# uRinks_v2_0.net
KiCad netlist of a schematic drawn in EAGLE
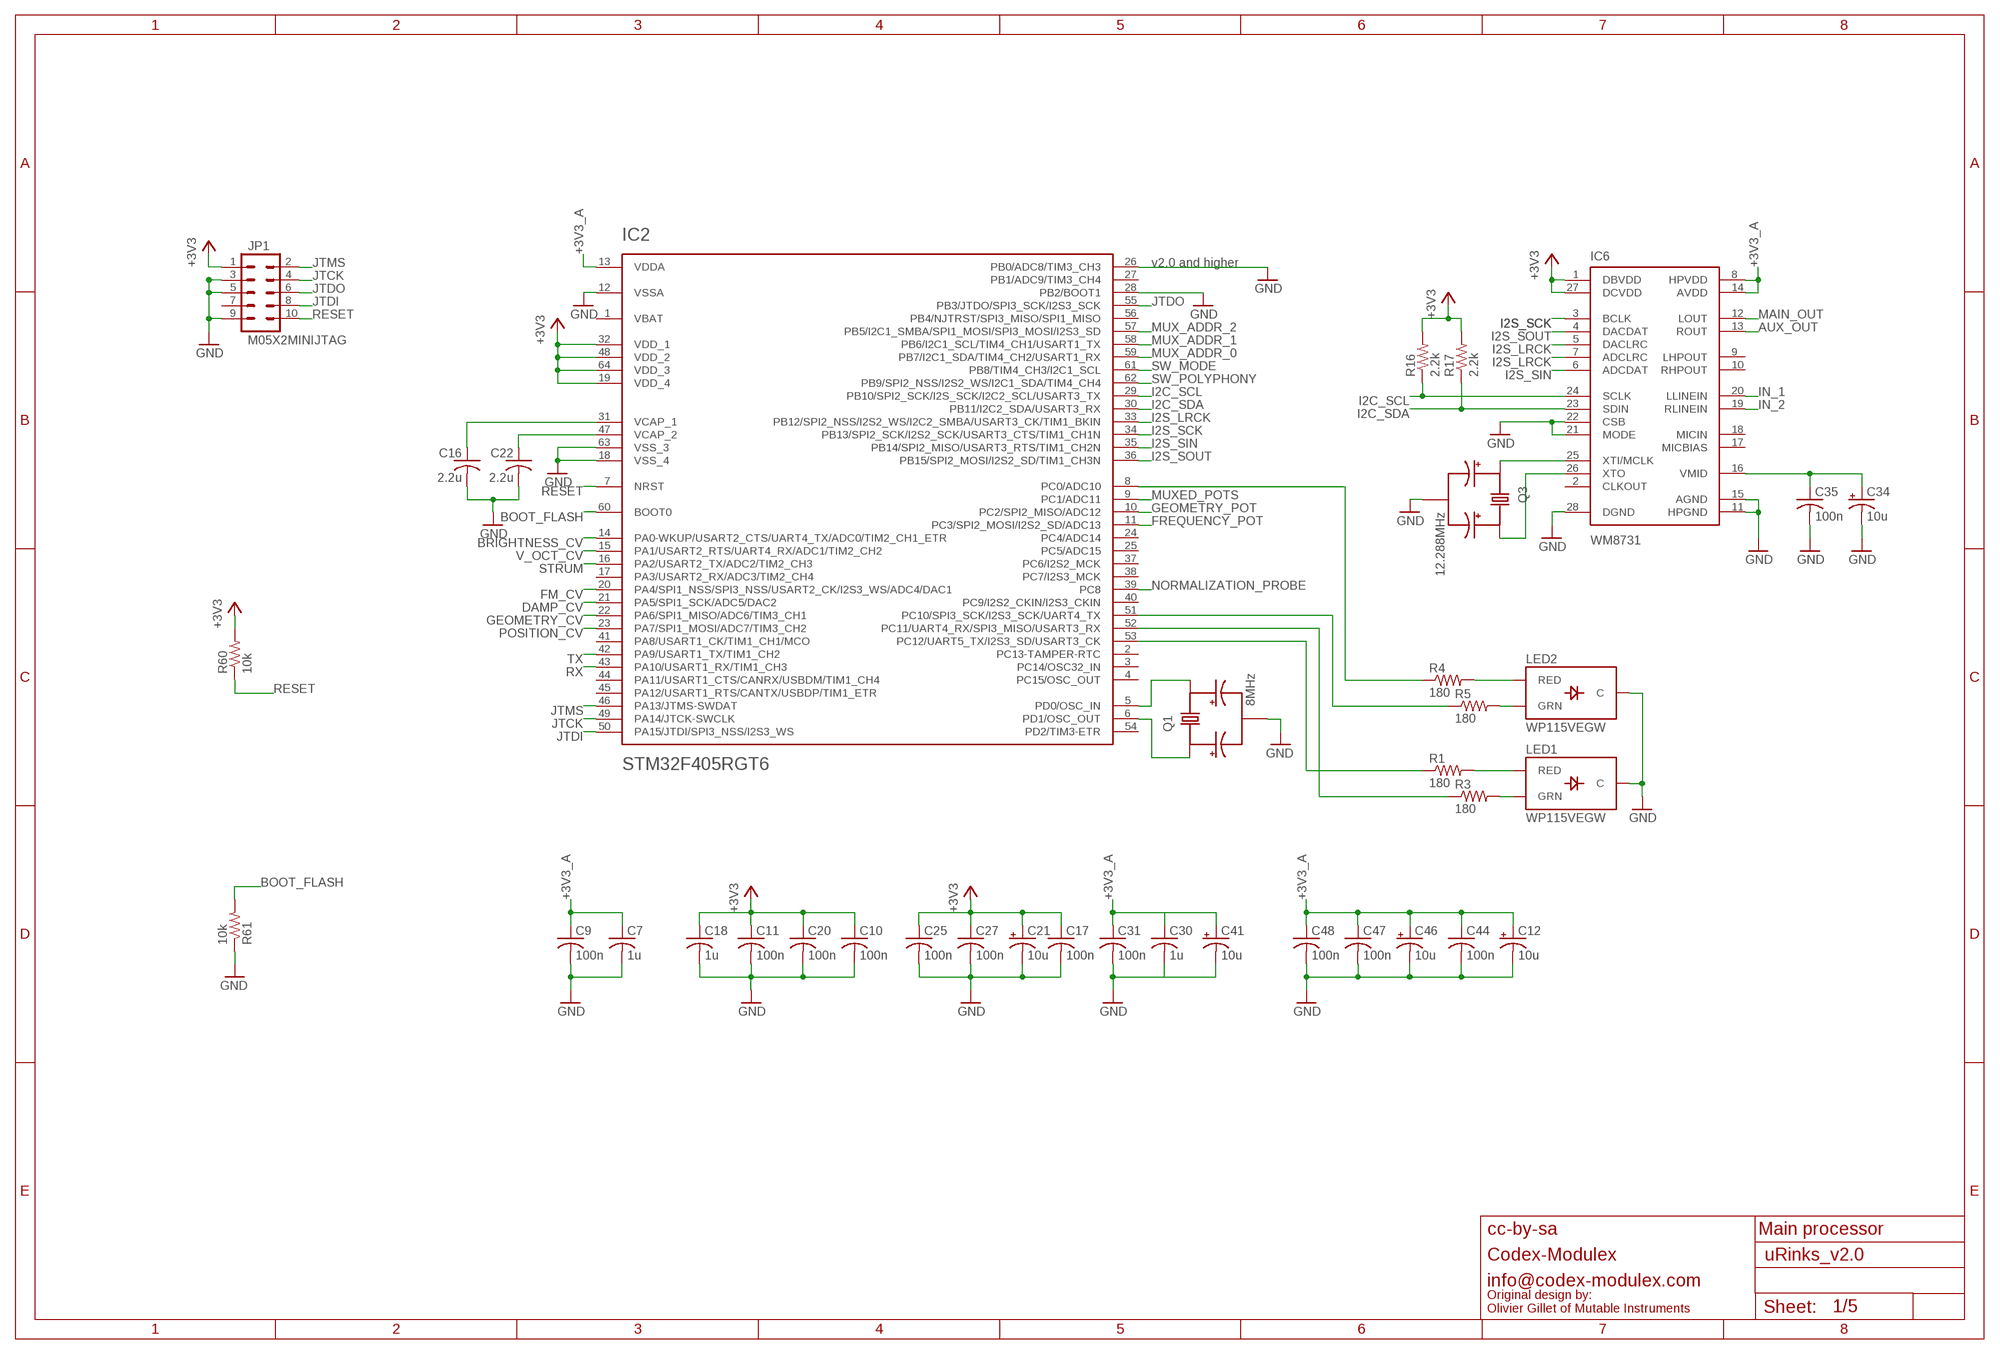
[diagram p0: schematic, sheet 1]
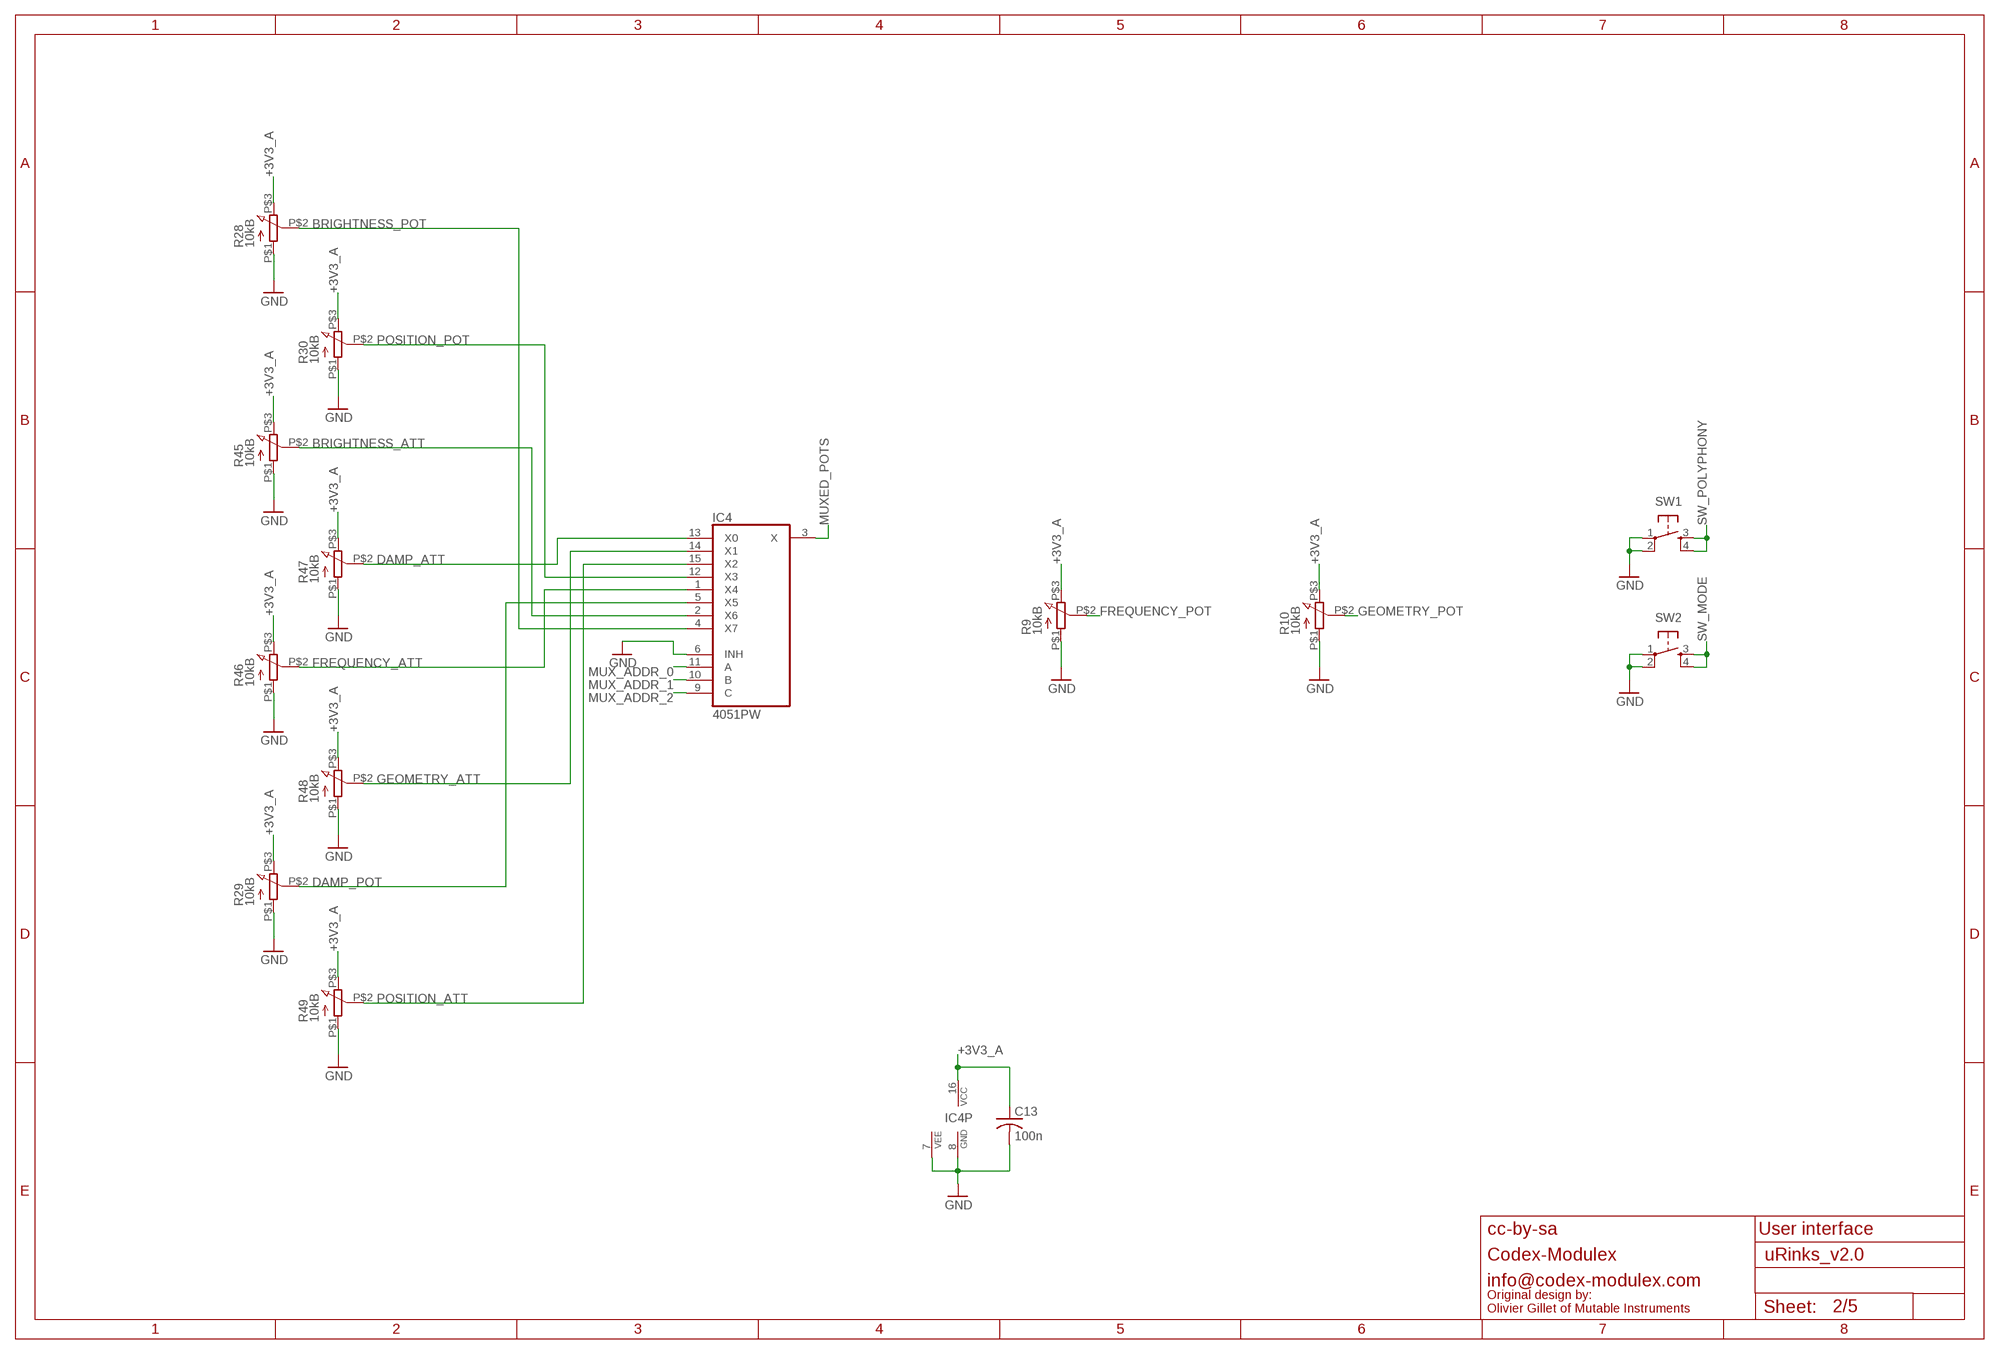
[diagram p1: schematic, sheet 2]
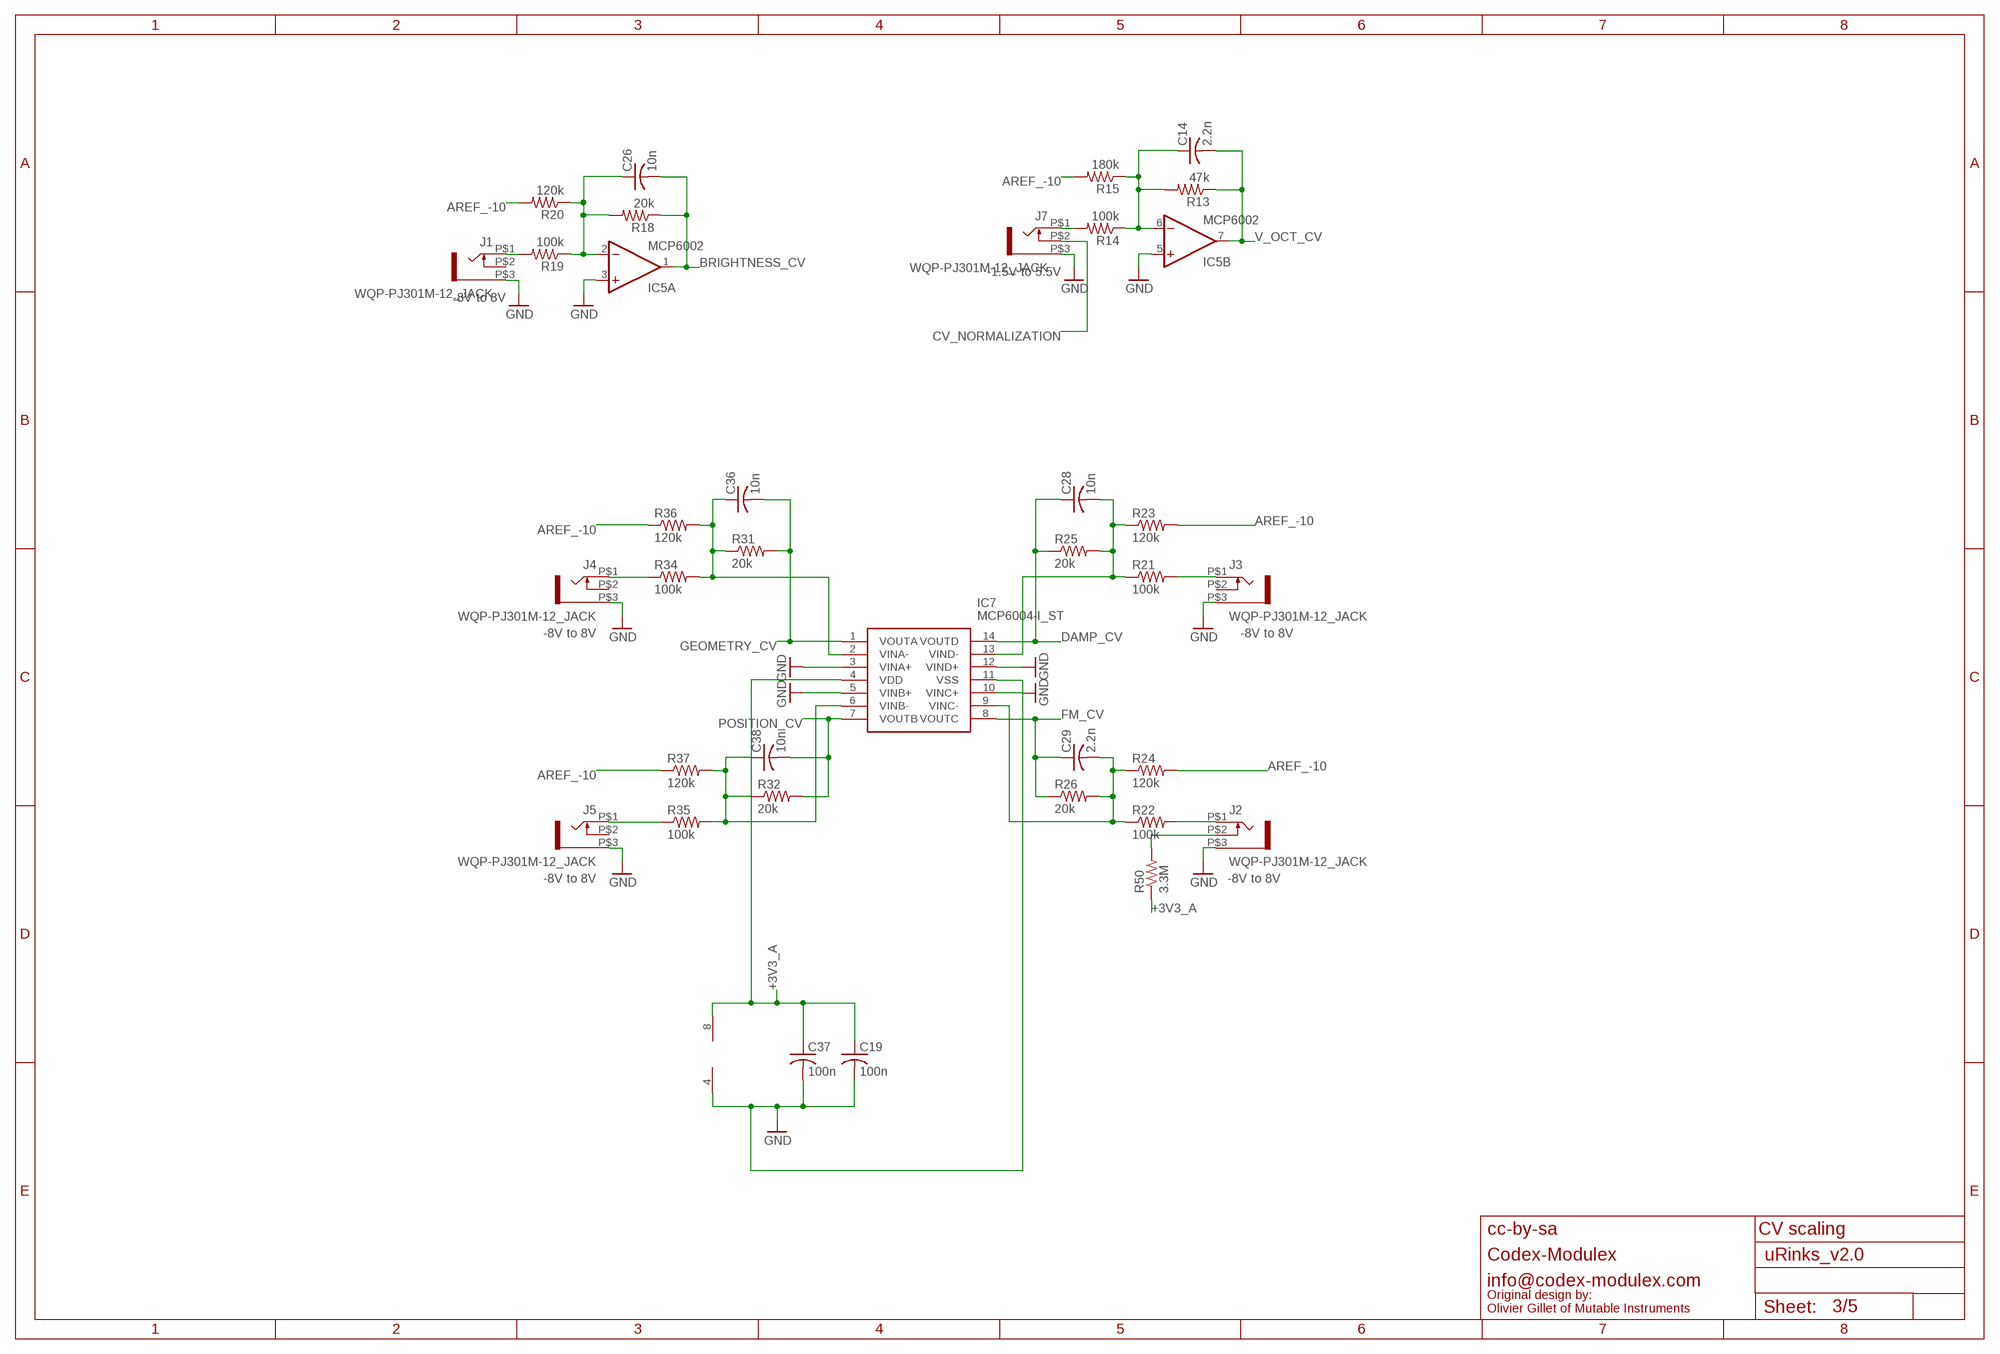
[diagram p2: schematic, sheet 3]
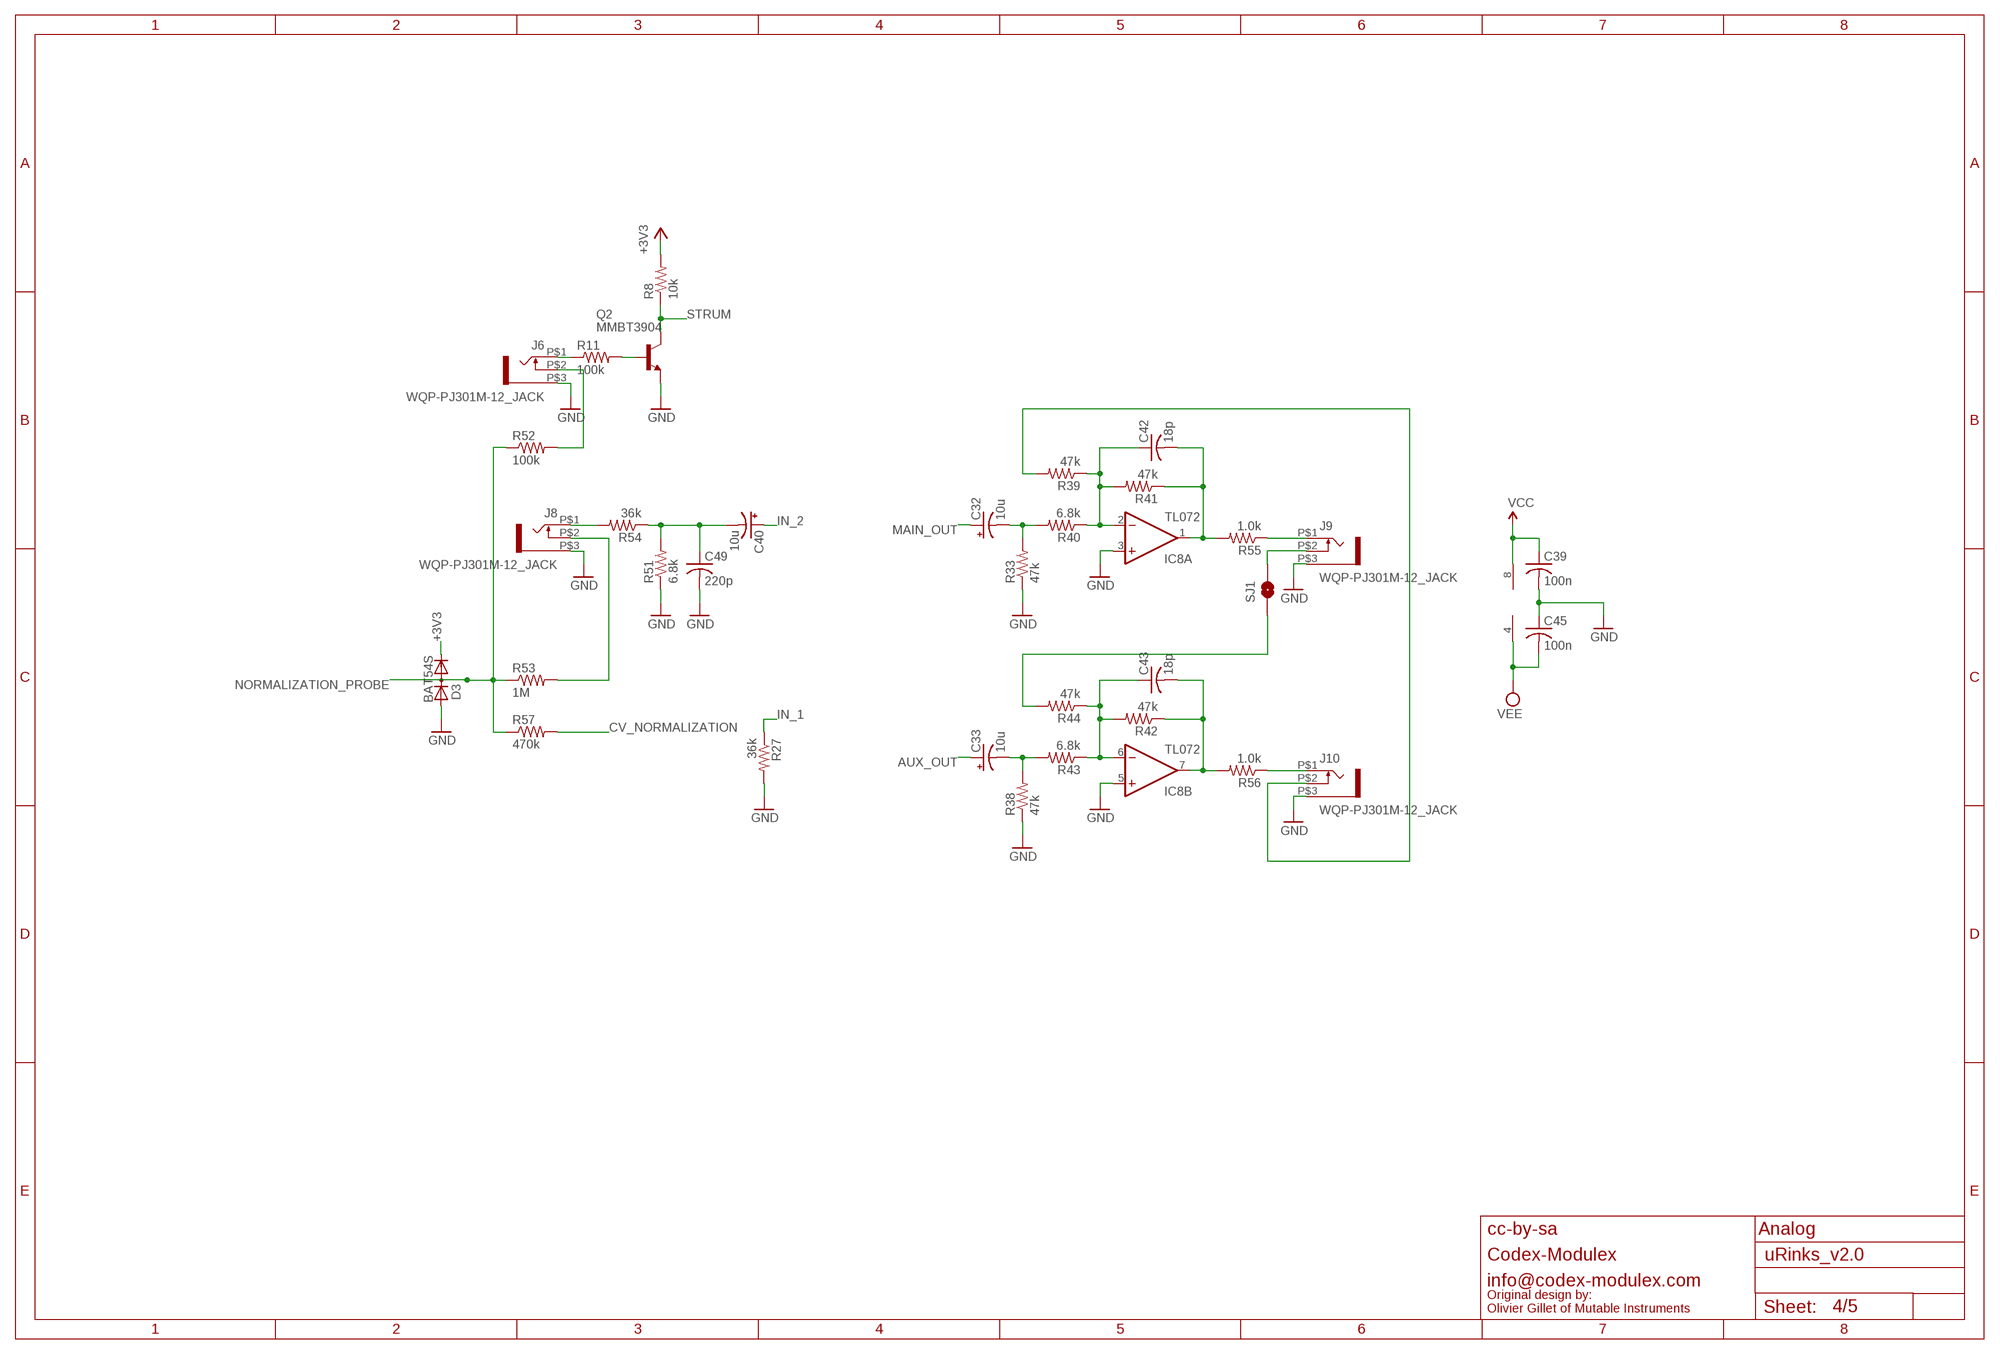
[diagram p3: schematic, sheet 4]
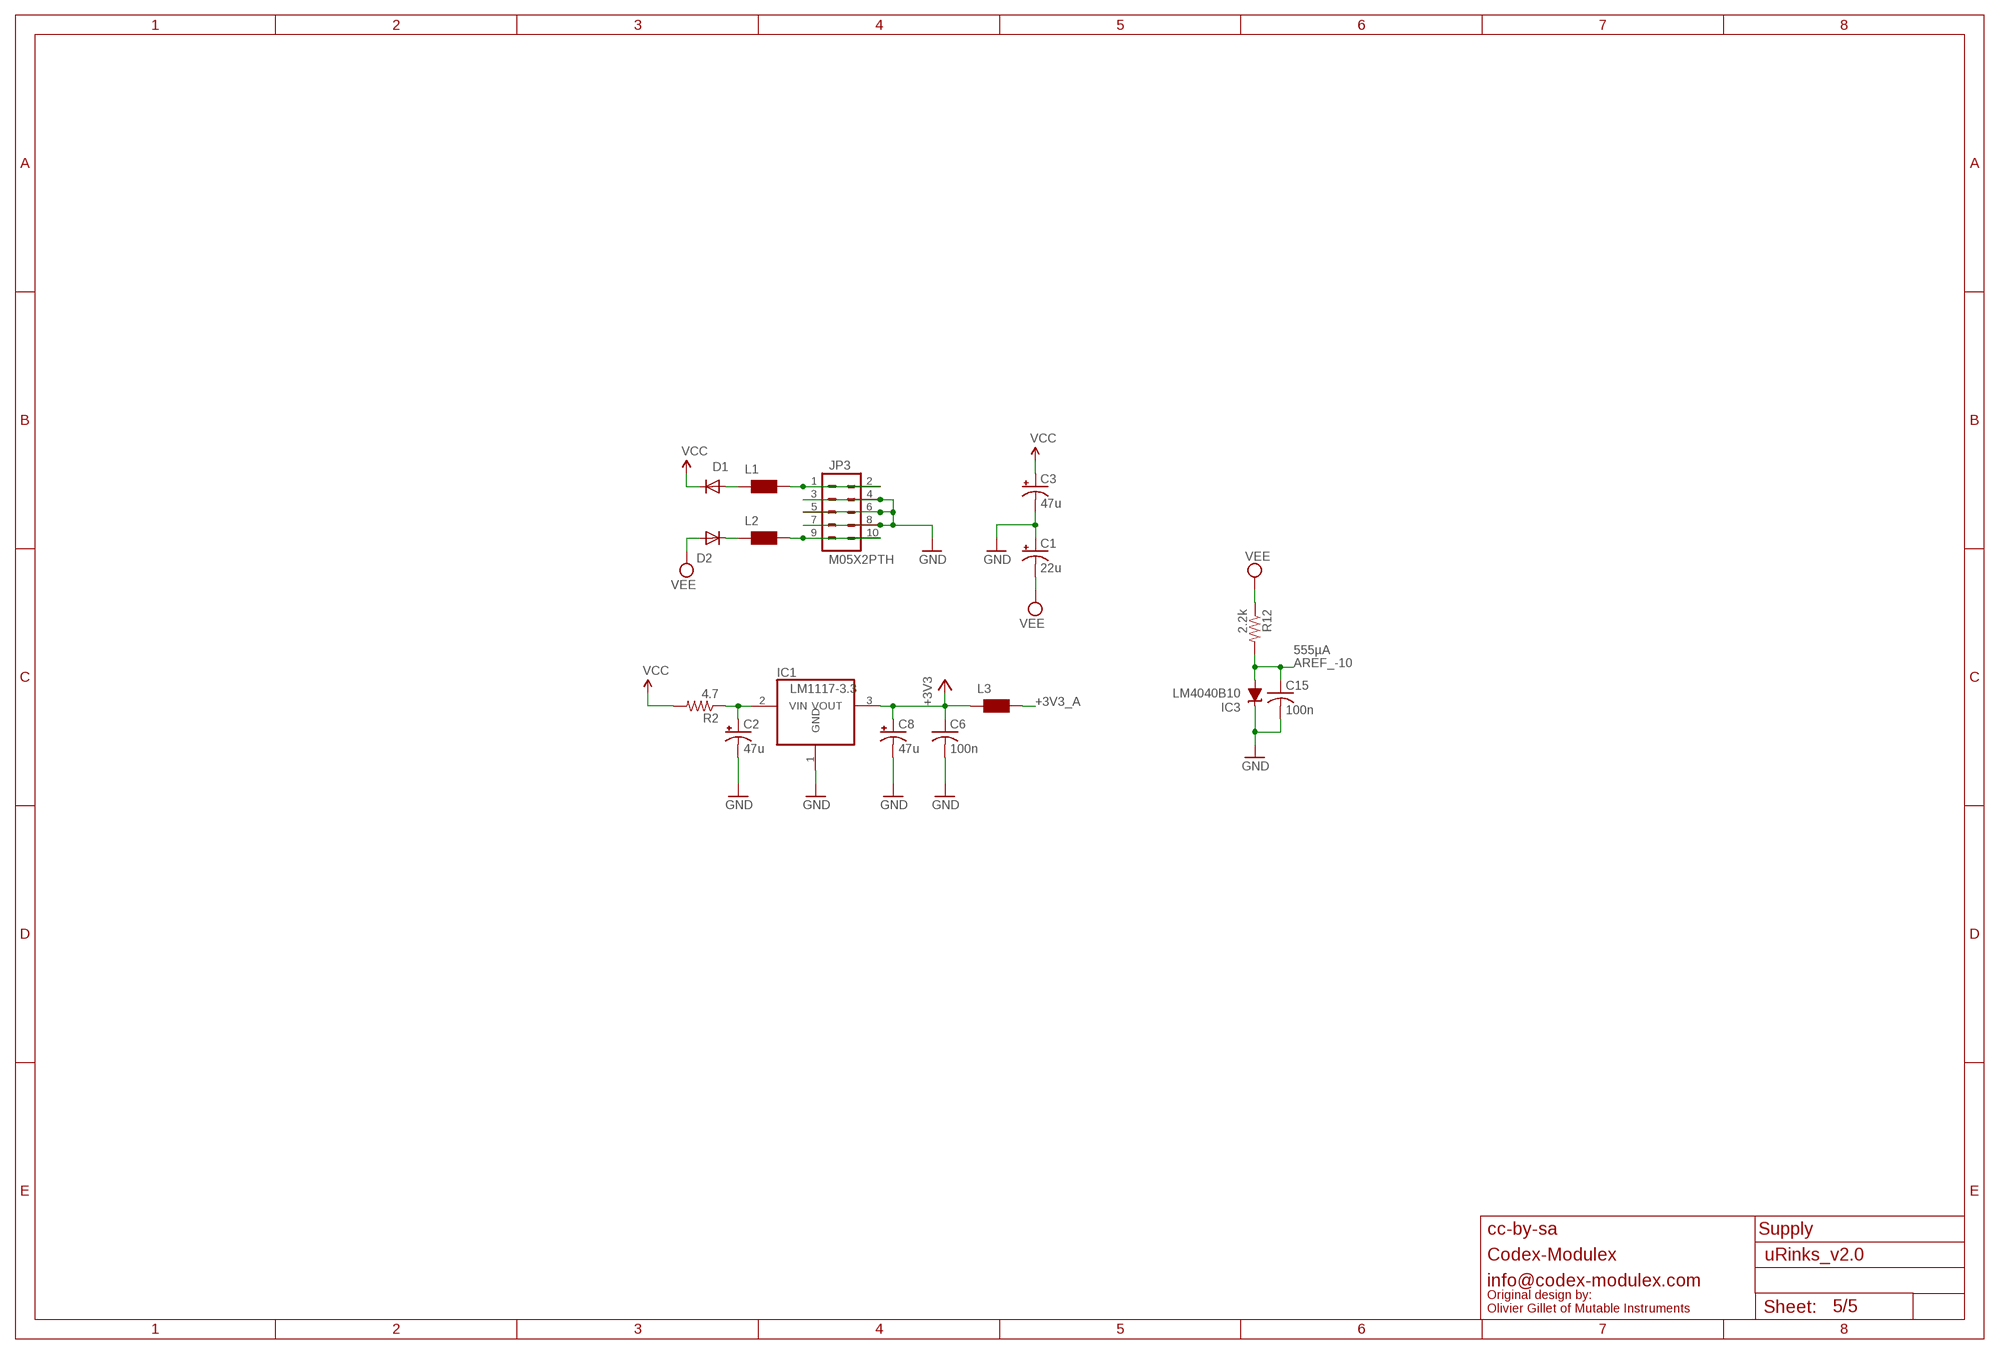
[diagram p4: schematic, sheet 5]

(export (version "E")
  (design (tool "Eeschema 10.0.6"))
  (components
    (comp (ref "C13")
      (value "100n")
      (footprint "eagle-import:C0603")
      (libsource (lib "eagle-import") (part "C-USC0603"))
    )
    (comp (ref "IC4")
      (value "4051PW")
      (footprint "eagle-import:TSSOP16")
      (libsource (lib "eagle-import") (part "4051PW"))
    )
    (comp (ref "R9")
      (value "10kB")
      (footprint "eagle-import:INSTRUO_Q-POT2")
      (libsource (lib "eagle-import") (part "INSTRUO_Q-POT2"))
    )
    (comp (ref "R10")
      (value "10kB")
      (footprint "eagle-import:INSTRUO_Q-POT2")
      (libsource (lib "eagle-import") (part "INSTRUO_Q-POT2"))
    )
    (comp (ref "R28")
      (value "10kB")
      (footprint "eagle-import:INSTRUO_Q-POT2")
      (libsource (lib "eagle-import") (part "INSTRUO_Q-POT2"))
    )
    (comp (ref "R29")
      (value "10kB")
      (footprint "eagle-import:INSTRUO_Q-POT2")
      (libsource (lib "eagle-import") (part "INSTRUO_Q-POT2"))
    )
    (comp (ref "R30")
      (value "10kB")
      (footprint "eagle-import:INSTRUO_Q-POT2")
      (libsource (lib "eagle-import") (part "INSTRUO_Q-POT2"))
    )
    (comp (ref "R45")
      (value "10kB")
      (footprint "eagle-import:INSTRUO_Q-POT2")
      (libsource (lib "eagle-import") (part "INSTRUO_Q-POT2"))
    )
    (comp (ref "R46")
      (value "10kB")
      (footprint "eagle-import:INSTRUO_Q-POT2")
      (libsource (lib "eagle-import") (part "INSTRUO_Q-POT2"))
    )
    (comp (ref "R47")
      (value "10kB")
      (footprint "eagle-import:INSTRUO_Q-POT2")
      (libsource (lib "eagle-import") (part "INSTRUO_Q-POT2"))
    )
    (comp (ref "R48")
      (value "10kB")
      (footprint "eagle-import:INSTRUO_Q-POT2")
      (libsource (lib "eagle-import") (part "INSTRUO_Q-POT2"))
    )
    (comp (ref "R49")
      (value "10kB")
      (footprint "eagle-import:INSTRUO_Q-POT2")
      (libsource (lib "eagle-import") (part "INSTRUO_Q-POT2"))
    )
    (comp (ref "SW1")
      (value "TAC_SWITCHPTH")
      (footprint "eagle-import:TACTILE-PTH")
      (libsource (lib "eagle-import") (part "TAC_SWITCHPTH"))
    )
    (comp (ref "SW2")
      (value "TAC_SWITCHPTH")
      (footprint "eagle-import:TACTILE-PTH")
      (libsource (lib "eagle-import") (part "TAC_SWITCHPTH"))
    )
    (comp (ref "C1")
      (value "22u")
      (footprint "eagle-import:PANASONIC_C")
      (libsource (lib "eagle-import") (part "CPOL-USC"))
    )
    (comp (ref "C2")
      (value "47u")
      (footprint "eagle-import:PANASONIC_D")
      (libsource (lib "eagle-import") (part "CPOL-USD"))
    )
    (comp (ref "C3")
      (value "47u")
      (footprint "eagle-import:PANASONIC_D")
      (libsource (lib "eagle-import") (part "CPOL-USD"))
    )
    (comp (ref "C6")
      (value "100n")
      (footprint "eagle-import:C0603")
      (libsource (lib "eagle-import") (part "C-USC0603"))
    )
    (comp (ref "C8")
      (value "47u")
      (footprint "eagle-import:PANASONIC_D")
      (libsource (lib "eagle-import") (part "CPOL-USD"))
    )
    (comp (ref "C15")
      (value "100n")
      (footprint "eagle-import:C0603")
      (libsource (lib "eagle-import") (part "C-USC0603"))
    )
    (comp (ref "D1")
      (value "1N5819HW")
      (footprint "eagle-import:SOD123")
      (libsource (lib "eagle-import") (part "DIODE-SOD123"))
    )
    (comp (ref "D2")
      (value "1N5819HW")
      (footprint "eagle-import:SOD123")
      (libsource (lib "eagle-import") (part "DIODE-SOD123"))
    )
    (comp (ref "IC1")
      (value "LM1117-3.3")
      (footprint "eagle-import:TO252")
      (libsource (lib "eagle-import") (part "REG1117T"))
    )
    (comp (ref "IC3")
      (value "LM4040B10")
      (footprint "eagle-import:DBZ_R-PDSO-G3")
      (libsource (lib "eagle-import") (part "LM4041DBZB12"))
    )
    (comp (ref "JP3")
      (value "M05X2PTH")
      (footprint "eagle-import:AVR_ICSP")
      (libsource (lib "eagle-import") (part "M05X2PTH"))
    )
    (comp (ref "L1")
      (value "WE-CBF_0603")
      (footprint "eagle-import:0603")
      (libsource (lib "eagle-import") (part "WE-CBF_0603"))
    )
    (comp (ref "L2")
      (value "WE-CBF_0603")
      (footprint "eagle-import:0603")
      (libsource (lib "eagle-import") (part "WE-CBF_0603"))
    )
    (comp (ref "L3")
      (value "WE-CBF_0603")
      (footprint "eagle-import:0603")
      (libsource (lib "eagle-import") (part "WE-CBF_0603"))
    )
    (comp (ref "R2")
      (value "4.7")
      (footprint "eagle-import:R1206")
      (libsource (lib "eagle-import") (part "R-US_R1206"))
    )
    (comp (ref "R12")
      (value "2.2k")
      (footprint "eagle-import:R0603")
      (libsource (lib "eagle-import") (part "R-US_R0603"))
    )
    (comp (ref "C32")
      (value "10u")
      (footprint "eagle-import:PANASONIC_A")
      (libsource (lib "eagle-import") (part "CPOL-USA"))
    )
    (comp (ref "C33")
      (value "10u")
      (footprint "eagle-import:PANASONIC_A")
      (libsource (lib "eagle-import") (part "CPOL-USA"))
    )
    (comp (ref "C39")
      (value "100n")
      (footprint "eagle-import:C0603")
      (libsource (lib "eagle-import") (part "C-USC0603"))
    )
    (comp (ref "C40")
      (value "10u")
      (footprint "eagle-import:PANASONIC_A")
      (libsource (lib "eagle-import") (part "CPOL-USA"))
    )
    (comp (ref "C42")
      (value "18p")
      (footprint "eagle-import:C0603")
      (libsource (lib "eagle-import") (part "C-USC0603"))
    )
    (comp (ref "C43")
      (value "18p")
      (footprint "eagle-import:C0603")
      (libsource (lib "eagle-import") (part "C-USC0603"))
    )
    (comp (ref "C45")
      (value "100n")
      (footprint "eagle-import:C0603")
      (libsource (lib "eagle-import") (part "C-USC0603"))
    )
    (comp (ref "C49")
      (value "220p")
      (footprint "eagle-import:C0603")
      (libsource (lib "eagle-import") (part "C-USC0603"))
    )
    (comp (ref "D3")
      (value "BAT54S")
      (footprint "eagle-import:SOT23")
      (libsource (lib "eagle-import") (part "DIODE_2CACA-SOT23"))
    )
    (comp (ref "IC8")
      (value "TL072")
      (footprint "eagle-import:SO08")
      (libsource (lib "eagle-import") (part "og-linear_TL072D"))
    )
    (comp (ref "J6")
      (value "WQP-PJ301M-12_JACK")
      (footprint "eagle-import:WQP-PJ301M-12_JACK")
      (libsource (lib "eagle-import") (part "WQP-PJ301M-12_JACK"))
    )
    (comp (ref "J8")
      (value "WQP-PJ301M-12_JACK")
      (footprint "eagle-import:WQP-PJ301M-12_JACK")
      (libsource (lib "eagle-import") (part "WQP-PJ301M-12_JACK"))
    )
    (comp (ref "J9")
      (value "WQP-PJ301M-12_JACK")
      (footprint "eagle-import:WQP-PJ301M-12_JACK")
      (libsource (lib "eagle-import") (part "WQP-PJ301M-12_JACK"))
    )
    (comp (ref "J10")
      (value "WQP-PJ301M-12_JACK")
      (footprint "eagle-import:WQP-PJ301M-12_JACK")
      (libsource (lib "eagle-import") (part "WQP-PJ301M-12_JACK"))
    )
    (comp (ref "Q2")
      (value "MMBT3904")
      (footprint "eagle-import:SOT23-BEC")
      (libsource (lib "eagle-import") (part "-NPN-SOT23-BECMMBT3904LT1"))
    )
    (comp (ref "R8")
      (value "10k")
      (footprint "eagle-import:R0603")
      (libsource (lib "eagle-import") (part "R-US_R0603"))
    )
    (comp (ref "R11")
      (value "100k")
      (footprint "eagle-import:R0603")
      (libsource (lib "eagle-import") (part "R-US_R0603"))
    )
    (comp (ref "R27")
      (value "36k")
      (footprint "eagle-import:R0603")
      (libsource (lib "eagle-import") (part "R-US_R0603"))
    )
    (comp (ref "R33")
      (value "47k")
      (footprint "eagle-import:R0603")
      (libsource (lib "eagle-import") (part "R-US_R0603"))
    )
    (comp (ref "R38")
      (value "47k")
      (footprint "eagle-import:R0603")
      (libsource (lib "eagle-import") (part "R-US_R0603"))
    )
    (comp (ref "R39")
      (value "47k")
      (footprint "eagle-import:R0603")
      (libsource (lib "eagle-import") (part "R-US_R0603"))
    )
    (comp (ref "R40")
      (value "6.8k")
      (footprint "eagle-import:R0603")
      (libsource (lib "eagle-import") (part "R-US_R0603"))
    )
    (comp (ref "R41")
      (value "47k")
      (footprint "eagle-import:R0603")
      (libsource (lib "eagle-import") (part "R-US_R0603"))
    )
    (comp (ref "R42")
      (value "47k")
      (footprint "eagle-import:R0603")
      (libsource (lib "eagle-import") (part "R-US_R0603"))
    )
    (comp (ref "R43")
      (value "6.8k")
      (footprint "eagle-import:R0603")
      (libsource (lib "eagle-import") (part "R-US_R0603"))
    )
    (comp (ref "R44")
      (value "47k")
      (footprint "eagle-import:R0603")
      (libsource (lib "eagle-import") (part "R-US_R0603"))
    )
    (comp (ref "R51")
      (value "6.8k")
      (footprint "eagle-import:R0603")
      (libsource (lib "eagle-import") (part "R-US_R0603"))
    )
    (comp (ref "R52")
      (value "100k")
      (footprint "eagle-import:R0603")
      (libsource (lib "eagle-import") (part "R-US_R0603"))
    )
    (comp (ref "R53")
      (value "1M")
      (footprint "eagle-import:R0603")
      (libsource (lib "eagle-import") (part "R-US_R0603"))
    )
    (comp (ref "R54")
      (value "36k")
      (footprint "eagle-import:R0603")
      (libsource (lib "eagle-import") (part "R-US_R0603"))
    )
    (comp (ref "R55")
      (value "1.0k")
      (footprint "eagle-import:R0603")
      (libsource (lib "eagle-import") (part "R-US_R0603"))
    )
    (comp (ref "R56")
      (value "1.0k")
      (footprint "eagle-import:R0603")
      (libsource (lib "eagle-import") (part "R-US_R0603"))
    )
    (comp (ref "R57")
      (value "470k")
      (footprint "eagle-import:R0603")
      (libsource (lib "eagle-import") (part "R-US_R0603"))
    )
    (comp (ref "SJ1")
      (value "SOLDERJUMPERNC2")
      (footprint "eagle-import:SJ_2S-NOTRACE")
      (libsource (lib "eagle-import") (part "SOLDERJUMPERNC2"))
    )
    (comp (ref "C14")
      (value "2.2n")
      (footprint "eagle-import:C0603")
      (libsource (lib "eagle-import") (part "C-USC0603"))
    )
    (comp (ref "C19")
      (value "100n")
      (footprint "eagle-import:C0603")
      (libsource (lib "eagle-import") (part "C-USC0603"))
    )
    (comp (ref "C26")
      (value "10n")
      (footprint "eagle-import:C0603")
      (libsource (lib "eagle-import") (part "C-USC0603"))
    )
    (comp (ref "C28")
      (value "10n")
      (footprint "eagle-import:C0603")
      (libsource (lib "eagle-import") (part "resistor_348_C-USC0603"))
    )
    (comp (ref "C29")
      (value "2.2n")
      (footprint "eagle-import:C0603")
      (libsource (lib "eagle-import") (part "resistor_348_C-USC0603"))
    )
    (comp (ref "C36")
      (value "10n")
      (footprint "eagle-import:C0603")
      (libsource (lib "eagle-import") (part "resistor_348_C-USC0603"))
    )
    (comp (ref "C37")
      (value "100n")
      (footprint "eagle-import:C0603")
      (libsource (lib "eagle-import") (part "C-USC0603"))
    )
    (comp (ref "C38")
      (value "10n")
      (footprint "eagle-import:C0603")
      (libsource (lib "eagle-import") (part "resistor_348_C-USC0603"))
    )
    (comp (ref "IC5")
      (value "MCP6002")
      (footprint "eagle-import:SO08")
      (libsource (lib "eagle-import") (part "TL072D"))
    )
    (comp (ref "IC7")
      (value "MCP6004-I_ST")
      (footprint "eagle-import:SOP65P640X120-14N")
      (fields
        (field (name "MANUFACTURER_PART_NUMBER") "MCP6004-I/ST")
        (field (name "MOUSER_PART_NUMBER") "579-MCP6004-I/ST")
      )
      (libsource (lib "eagle-import") (part "MCP6004-I_ST"))
    )
    (comp (ref "J1")
      (value "WQP-PJ301M-12_JACK")
      (footprint "eagle-import:WQP-PJ301M-12_JACK")
      (libsource (lib "eagle-import") (part "WQP-PJ301M-12_JACK"))
    )
    (comp (ref "J2")
      (value "WQP-PJ301M-12_JACK")
      (footprint "eagle-import:WQP-PJ301M-12_JACK")
      (libsource (lib "eagle-import") (part "WQP-PJ301M-12_JACK"))
    )
    (comp (ref "J3")
      (value "WQP-PJ301M-12_JACK")
      (footprint "eagle-import:WQP-PJ301M-12_JACK")
      (libsource (lib "eagle-import") (part "WQP-PJ301M-12_JACK"))
    )
    (comp (ref "J4")
      (value "WQP-PJ301M-12_JACK")
      (footprint "eagle-import:WQP-PJ301M-12_JACK")
      (libsource (lib "eagle-import") (part "WQP-PJ301M-12_JACK"))
    )
    (comp (ref "J5")
      (value "WQP-PJ301M-12_JACK")
      (footprint "eagle-import:WQP-PJ301M-12_JACK")
      (libsource (lib "eagle-import") (part "WQP-PJ301M-12_JACK"))
    )
    (comp (ref "J7")
      (value "WQP-PJ301M-12_JACK")
      (footprint "eagle-import:WQP-PJ301M-12_JACK")
      (libsource (lib "eagle-import") (part "WQP-PJ301M-12_JACK"))
    )
    (comp (ref "R13")
      (value "47k")
      (footprint "eagle-import:R0603")
      (libsource (lib "eagle-import") (part "R-US_R0603"))
    )
    (comp (ref "R14")
      (value "100k")
      (footprint "eagle-import:R0603")
      (libsource (lib "eagle-import") (part "R-US_R0603"))
    )
    (comp (ref "R15")
      (value "180k")
      (footprint "eagle-import:R0603")
      (libsource (lib "eagle-import") (part "R-US_R0603"))
    )
    (comp (ref "R18")
      (value "20k")
      (footprint "eagle-import:R0603")
      (libsource (lib "eagle-import") (part "R-US_R0603"))
    )
    (comp (ref "R19")
      (value "100k")
      (footprint "eagle-import:R0603")
      (libsource (lib "eagle-import") (part "R-US_R0603"))
    )
    (comp (ref "R20")
      (value "120k")
      (footprint "eagle-import:R0603")
      (libsource (lib "eagle-import") (part "R-US_R0603"))
    )
    (comp (ref "R21")
      (value "100k")
      (footprint "eagle-import:R0603")
      (libsource (lib "eagle-import") (part "resistor_348_R-US_R0603"))
    )
    (comp (ref "R22")
      (value "100k")
      (footprint "eagle-import:R0603")
      (libsource (lib "eagle-import") (part "resistor_348_R-US_R0603"))
    )
    (comp (ref "R23")
      (value "120k")
      (footprint "eagle-import:R0603")
      (libsource (lib "eagle-import") (part "resistor_348_R-US_R0603"))
    )
    (comp (ref "R24")
      (value "120k")
      (footprint "eagle-import:R0603")
      (libsource (lib "eagle-import") (part "resistor_348_R-US_R0603"))
    )
    (comp (ref "R25")
      (value "20k")
      (footprint "eagle-import:R0603")
      (libsource (lib "eagle-import") (part "resistor_348_R-US_R0603"))
    )
    (comp (ref "R26")
      (value "20k")
      (footprint "eagle-import:R0603")
      (libsource (lib "eagle-import") (part "resistor_348_R-US_R0603"))
    )
    (comp (ref "R31")
      (value "20k")
      (footprint "eagle-import:R0603")
      (libsource (lib "eagle-import") (part "resistor_348_R-US_R0603"))
    )
    (comp (ref "R32")
      (value "20k")
      (footprint "eagle-import:R0603")
      (libsource (lib "eagle-import") (part "resistor_348_R-US_R0603"))
    )
    (comp (ref "R34")
      (value "100k")
      (footprint "eagle-import:R0603")
      (libsource (lib "eagle-import") (part "resistor_348_R-US_R0603"))
    )
    (comp (ref "R35")
      (value "100k")
      (footprint "eagle-import:R0603")
      (libsource (lib "eagle-import") (part "resistor_348_R-US_R0603"))
    )
    (comp (ref "R36")
      (value "120k")
      (footprint "eagle-import:R0603")
      (libsource (lib "eagle-import") (part "resistor_348_R-US_R0603"))
    )
    (comp (ref "R37")
      (value "120k")
      (footprint "eagle-import:R0603")
      (libsource (lib "eagle-import") (part "resistor_348_R-US_R0603"))
    )
    (comp (ref "R50")
      (value "3.3M")
      (footprint "eagle-import:R0603")
      (libsource (lib "eagle-import") (part "resistor_348_R-US_R0603"))
    )
    (comp (ref "C7")
      (value "1u")
      (footprint "eagle-import:C0603")
      (libsource (lib "eagle-import") (part "C-USC0603"))
    )
    (comp (ref "C9")
      (value "100n")
      (footprint "eagle-import:C0603")
      (libsource (lib "eagle-import") (part "C-USC0603"))
    )
    (comp (ref "C10")
      (value "100n")
      (footprint "eagle-import:C0603")
      (libsource (lib "eagle-import") (part "C-USC0603"))
    )
    (comp (ref "C11")
      (value "100n")
      (footprint "eagle-import:C0603")
      (libsource (lib "eagle-import") (part "C-USC0603"))
    )
    (comp (ref "C12")
      (value "10u")
      (footprint "eagle-import:PANASONIC_A")
      (libsource (lib "eagle-import") (part "CPOL-USA"))
    )
    (comp (ref "C16")
      (value "2.2u")
      (footprint "eagle-import:C0805")
      (libsource (lib "eagle-import") (part "C-USC0805"))
    )
    (comp (ref "C17")
      (value "100n")
      (footprint "eagle-import:C0603")
      (libsource (lib "eagle-import") (part "C-USC0603"))
    )
    (comp (ref "C18")
      (value "1u")
      (footprint "eagle-import:C0603")
      (libsource (lib "eagle-import") (part "C-USC0603"))
    )
    (comp (ref "C20")
      (value "100n")
      (footprint "eagle-import:C0603")
      (libsource (lib "eagle-import") (part "C-USC0603"))
    )
    (comp (ref "C21")
      (value "10u")
      (footprint "eagle-import:PANASONIC_A")
      (libsource (lib "eagle-import") (part "CPOL-USA"))
    )
    (comp (ref "C22")
      (value "2.2u")
      (footprint "eagle-import:C0805")
      (libsource (lib "eagle-import") (part "C-USC0805"))
    )
    (comp (ref "C25")
      (value "100n")
      (footprint "eagle-import:C0603")
      (libsource (lib "eagle-import") (part "C-USC0603"))
    )
    (comp (ref "C27")
      (value "100n")
      (footprint "eagle-import:C0603")
      (libsource (lib "eagle-import") (part "C-USC0603"))
    )
    (comp (ref "C30")
      (value "1u")
      (footprint "eagle-import:C0603")
      (libsource (lib "eagle-import") (part "C-USC0603"))
    )
    (comp (ref "C31")
      (value "100n")
      (footprint "eagle-import:C0603")
      (libsource (lib "eagle-import") (part "C-USC0603"))
    )
    (comp (ref "C34")
      (value "10u")
      (footprint "eagle-import:PANASONIC_A")
      (libsource (lib "eagle-import") (part "CPOL-USA"))
    )
    (comp (ref "C35")
      (value "100n")
      (footprint "eagle-import:C0603")
      (libsource (lib "eagle-import") (part "C-USC0603"))
    )
    (comp (ref "C41")
      (value "10u")
      (footprint "eagle-import:PANASONIC_A")
      (libsource (lib "eagle-import") (part "CPOL-USA"))
    )
    (comp (ref "C44")
      (value "100n")
      (footprint "eagle-import:C0603")
      (libsource (lib "eagle-import") (part "C-USC0603"))
    )
    (comp (ref "C46")
      (value "10u")
      (footprint "eagle-import:PANASONIC_A")
      (libsource (lib "eagle-import") (part "CPOL-USA"))
    )
    (comp (ref "C47")
      (value "100n")
      (footprint "eagle-import:C0603")
      (libsource (lib "eagle-import") (part "C-USC0603"))
    )
    (comp (ref "C48")
      (value "100n")
      (footprint "eagle-import:C0603")
      (libsource (lib "eagle-import") (part "C-USC0603"))
    )
    (comp (ref "IC2")
      (value "STM32F405RGT6")
      (footprint "eagle-import:TQFP-10X10-64")
      (libsource (lib "eagle-import") (part "STM32F20X"))
    )
    (comp (ref "IC6")
      (value "WM8731")
      (footprint "eagle-import:SSOP28")
      (libsource (lib "eagle-import") (part "WM8731"))
    )
    (comp (ref "JP1")
      (value "M05X2MINIJTAG")
      (footprint "eagle-import:2X5-1.27")
      (libsource (lib "eagle-import") (part "M05X2MINIJTAG"))
    )
    (comp (ref "LED1")
      (value "WP115VEGW")
      (footprint "eagle-import:LED-BICOLOR-THROUGHHOLE")
      (libsource (lib "eagle-import") (part "LED-BICOLOR-THROUGHHOLE"))
    )
    (comp (ref "LED2")
      (value "WP115VEGW")
      (footprint "eagle-import:LED-BICOLOR-THROUGHHOLE")
      (libsource (lib "eagle-import") (part "LED-BICOLOR-THROUGHHOLE"))
    )
    (comp (ref "Q1")
      (value "8MHz")
      (footprint "eagle-import:INSTRUO_CRYSTAL_SMALLER")
      (libsource (lib "eagle-import") (part "INSTRUO_CRYSTAL_SMALLER"))
    )
    (comp (ref "Q3")
      (value "12.288MHz")
      (footprint "eagle-import:INSTRUO_CRYSTAL_SMALLER")
      (libsource (lib "eagle-import") (part "INSTRUO_CRYSTAL_SMALLER"))
    )
    (comp (ref "R1")
      (value "180")
      (footprint "eagle-import:R0603")
      (libsource (lib "eagle-import") (part "R-US_R0603"))
    )
    (comp (ref "R3")
      (value "180")
      (footprint "eagle-import:R0603")
      (libsource (lib "eagle-import") (part "R-US_R0603"))
    )
    (comp (ref "R4")
      (value "180")
      (footprint "eagle-import:R0603")
      (libsource (lib "eagle-import") (part "R-US_R0603"))
    )
    (comp (ref "R5")
      (value "180")
      (footprint "eagle-import:R0603")
      (libsource (lib "eagle-import") (part "R-US_R0603"))
    )
    (comp (ref "R16")
      (value "2.2k")
      (footprint "eagle-import:R0603")
      (libsource (lib "eagle-import") (part "R-US_R0603"))
    )
    (comp (ref "R17")
      (value "2.2k")
      (footprint "eagle-import:R0603")
      (libsource (lib "eagle-import") (part "R-US_R0603"))
    )
    (comp (ref "R60")
      (value "10k")
      (footprint "eagle-import:R0603")
      (libsource (lib "eagle-import") (part "R-US_R0603"))
    )
    (comp (ref "R61")
      (value "10k")
      (footprint "eagle-import:R0603")
      (libsource (lib "eagle-import") (part "R-US_R0603"))
    )
  )
  (nets
    (net (code "1") (name "+3V3") (class "Default")
      (node (ref "C10") (pin "1") (pinfunction "1_1") (pintype "passive"))
      (node (ref "C11") (pin "1") (pinfunction "1_1") (pintype "passive"))
      (node (ref "C17") (pin "1") (pinfunction "1_1") (pintype "passive"))
      (node (ref "C18") (pin "1") (pinfunction "1_1") (pintype "passive"))
      (node (ref "C20") (pin "1") (pinfunction "1_1") (pintype "passive"))
      (node (ref "C21") (pin "+") (pinfunction "+_+") (pintype "passive"))
      (node (ref "C25") (pin "1") (pinfunction "1_1") (pintype "passive"))
      (node (ref "C27") (pin "1") (pinfunction "1_1") (pintype "passive"))
      (node (ref "C6") (pin "1") (pinfunction "1_1") (pintype "passive"))
      (node (ref "C8") (pin "+") (pinfunction "+_+") (pintype "passive"))
      (node (ref "D3") (pin "2") (pinfunction "C_2") (pintype "passive"))
      (node (ref "IC1") (pin "3") (pinfunction "VOUT_3") (pintype "output"))
      (node (ref "IC2") (pin "19") (pinfunction "VDD_4_19") (pintype "power_in"))
      (node (ref "IC2") (pin "32") (pinfunction "VDD_1_32") (pintype "power_in"))
      (node (ref "IC2") (pin "48") (pinfunction "VDD_2_48") (pintype "power_in"))
      (node (ref "IC2") (pin "64") (pinfunction "VDD_3_64") (pintype "power_in"))
      (node (ref "IC6") (pin "1") (pinfunction "DBVDD_1") (pintype "bidirectional"))
      (node (ref "IC6") (pin "27") (pinfunction "DCVDD_27") (pintype "bidirectional"))
      (node (ref "JP1") (pin "1") (pinfunction "1_1") (pintype "passive"))
      (node (ref "L3") (pin "1") (pinfunction "1_1") (pintype "passive"))
      (node (ref "R16") (pin "2") (pinfunction "2_2") (pintype "passive"))
      (node (ref "R17") (pin "2") (pinfunction "2_2") (pintype "passive"))
      (node (ref "R60") (pin "2") (pinfunction "2_2") (pintype "passive"))
      (node (ref "R8") (pin "2") (pinfunction "2_2") (pintype "passive"))
    )
    (net (code "2") (name "+3V3_A") (class "Default")
      (node (ref "C12") (pin "+") (pinfunction "+_+") (pintype "passive"))
      (node (ref "C13") (pin "1") (pinfunction "1_1") (pintype "passive"))
      (node (ref "C19") (pin "1") (pinfunction "1_1") (pintype "passive"))
      (node (ref "C30") (pin "1") (pinfunction "1_1") (pintype "passive"))
      (node (ref "C31") (pin "1") (pinfunction "1_1") (pintype "passive"))
      (node (ref "C37") (pin "1") (pinfunction "1_1") (pintype "passive"))
      (node (ref "C41") (pin "+") (pinfunction "+_+") (pintype "passive"))
      (node (ref "C44") (pin "1") (pinfunction "1_1") (pintype "passive"))
      (node (ref "C46") (pin "+") (pinfunction "+_+") (pintype "passive"))
      (node (ref "C47") (pin "1") (pinfunction "1_1") (pintype "passive"))
      (node (ref "C48") (pin "1") (pinfunction "1_1") (pintype "passive"))
      (node (ref "C7") (pin "1") (pinfunction "1_1") (pintype "passive"))
      (node (ref "C9") (pin "1") (pinfunction "1_1") (pintype "passive"))
      (node (ref "IC2") (pin "13") (pinfunction "VDDA_13") (pintype "power_in"))
      (node (ref "IC4") (pin "16") (pinfunction "VCC_16") (pintype "power_in"))
      (node (ref "IC5") (pin "8") (pinfunction "V+_8") (pintype "power_in"))
      (node (ref "IC6") (pin "14") (pinfunction "AVDD_14") (pintype "bidirectional"))
      (node (ref "IC6") (pin "8") (pinfunction "HPVDD_8") (pintype "bidirectional"))
      (node (ref "IC7") (pin "4") (pinfunction "VDD_4") (pintype "power_in"))
      (node (ref "L3") (pin "2") (pinfunction "2_2") (pintype "passive"))
      (node (ref "R10") (pin "P$3") (pinfunction "3_P$3") (pintype "passive"))
      (node (ref "R28") (pin "P$3") (pinfunction "3_P$3") (pintype "passive"))
      (node (ref "R29") (pin "P$3") (pinfunction "3_P$3") (pintype "passive"))
      (node (ref "R30") (pin "P$3") (pinfunction "3_P$3") (pintype "passive"))
      (node (ref "R45") (pin "P$3") (pinfunction "3_P$3") (pintype "passive"))
      (node (ref "R46") (pin "P$3") (pinfunction "3_P$3") (pintype "passive"))
      (node (ref "R47") (pin "P$3") (pinfunction "3_P$3") (pintype "passive"))
      (node (ref "R48") (pin "P$3") (pinfunction "3_P$3") (pintype "passive"))
      (node (ref "R49") (pin "P$3") (pinfunction "3_P$3") (pintype "passive"))
      (node (ref "R50") (pin "1") (pinfunction "1_1") (pintype "passive"))
      (node (ref "R9") (pin "P$3") (pinfunction "3_P$3") (pintype "passive"))
    )
    (net (code "3") (name "AREF_-10") (class "Default")
      (node (ref "C15") (pin "1") (pinfunction "1_1") (pintype "passive"))
      (node (ref "IC3") (pin "2") (pinfunction "A_2") (pintype "passive"))
      (node (ref "R12") (pin "2") (pinfunction "2_2") (pintype "passive"))
      (node (ref "R15") (pin "2") (pinfunction "2_2") (pintype "passive"))
      (node (ref "R20") (pin "2") (pinfunction "2_2") (pintype "passive"))
      (node (ref "R23") (pin "2") (pinfunction "2_2") (pintype "passive"))
      (node (ref "R24") (pin "2") (pinfunction "2_2") (pintype "passive"))
      (node (ref "R36") (pin "1") (pinfunction "1_1") (pintype "passive"))
      (node (ref "R37") (pin "1") (pinfunction "1_1") (pintype "passive"))
    )
    (net (code "4") (name "AUX_OUT") (class "Default")
      (node (ref "C33") (pin "+") (pinfunction "+_+") (pintype "passive"))
      (node (ref "IC6") (pin "13") (pinfunction "ROUT_13") (pintype "bidirectional"))
    )
    (net (code "5") (name "BOOT_FLASH") (class "Default")
      (node (ref "IC2") (pin "60") (pinfunction "BOOT0_60") (pintype "bidirectional"))
      (node (ref "R61") (pin "2") (pinfunction "2_2") (pintype "passive"))
    )
    (net (code "6") (name "BRIGHTNESS_ATT") (class "Default")
      (node (ref "IC4") (pin "2") (pinfunction "X6_2") (pintype "bidirectional"))
      (node (ref "R45") (pin "P$2") (pinfunction "2_P$2") (pintype "passive"))
    )
    (net (code "7") (name "BRIGHTNESS_CV") (class "Default")
      (node (ref "C26") (pin "2") (pinfunction "2_2") (pintype "passive"))
      (node (ref "IC2") (pin "14") (pinfunction "PA0-WKUP/USART2_CTS/UART4_TX/ADC0/TIM2_CH1_ETR_14") (pintype "bidirectional"))
      (node (ref "IC5") (pin "1") (pinfunction "OUT_1") (pintype "output"))
      (node (ref "R18") (pin "1") (pinfunction "1_1") (pintype "passive"))
    )
    (net (code "8") (name "BRIGHTNESS_POT") (class "Default")
      (node (ref "IC4") (pin "4") (pinfunction "X7_4") (pintype "bidirectional"))
      (node (ref "R28") (pin "P$2") (pinfunction "2_P$2") (pintype "passive"))
    )
    (net (code "9") (name "CV_NORMALIZATION") (class "Default")
      (node (ref "J7") (pin "P$2") (pinfunction "3_P$2") (pintype "passive"))
      (node (ref "R57") (pin "2") (pinfunction "2_2") (pintype "passive"))
    )
    (net (code "10") (name "DAMP_ATT") (class "Default")
      (node (ref "IC4") (pin "13") (pinfunction "X0_13") (pintype "bidirectional"))
      (node (ref "R47") (pin "P$2") (pinfunction "2_P$2") (pintype "passive"))
    )
    (net (code "11") (name "DAMP_CV") (class "Default")
      (node (ref "C28") (pin "1") (pinfunction "1_1") (pintype "passive"))
      (node (ref "IC2") (pin "21") (pinfunction "PA5/SPI1_SCK/ADC5/DAC2_21") (pintype "bidirectional"))
      (node (ref "IC7") (pin "14") (pinfunction "VOUTD_14") (pintype "output"))
      (node (ref "R25") (pin "1") (pinfunction "1_1") (pintype "passive"))
    )
    (net (code "12") (name "DAMP_POT") (class "Default")
      (node (ref "IC4") (pin "5") (pinfunction "X5_5") (pintype "bidirectional"))
      (node (ref "R29") (pin "P$2") (pinfunction "2_P$2") (pintype "passive"))
    )
    (net (code "13") (name "FM_CV") (class "Default")
      (node (ref "C29") (pin "1") (pinfunction "1_1") (pintype "passive"))
      (node (ref "IC2") (pin "20") (pinfunction "PA4/SPI1_NSS/SPI3_NSS/USART2_CK/I2S3_WS/ADC4/DAC1_20") (pintype "bidirectional"))
      (node (ref "IC7") (pin "8") (pinfunction "VOUTC_8") (pintype "output"))
      (node (ref "R26") (pin "1") (pinfunction "1_1") (pintype "passive"))
    )
    (net (code "14") (name "FREQUENCY_ATT") (class "Default")
      (node (ref "IC4") (pin "1") (pinfunction "X4_1") (pintype "bidirectional"))
      (node (ref "R46") (pin "P$2") (pinfunction "2_P$2") (pintype "passive"))
    )
    (net (code "15") (name "FREQUENCY_POT") (class "Default")
      (node (ref "IC2") (pin "11") (pinfunction "PC3/SPI2_MOSI/I2S2_SD/ADC13_11") (pintype "bidirectional"))
      (node (ref "R9") (pin "P$2") (pinfunction "2_P$2") (pintype "passive"))
    )
    (net (code "16") (name "GEOMETRY_ATT") (class "Default")
      (node (ref "IC4") (pin "14") (pinfunction "X1_14") (pintype "bidirectional"))
      (node (ref "R48") (pin "P$2") (pinfunction "2_P$2") (pintype "passive"))
    )
    (net (code "17") (name "GEOMETRY_CV") (class "Default")
      (node (ref "C36") (pin "2") (pinfunction "2_2") (pintype "passive"))
      (node (ref "IC2") (pin "22") (pinfunction "PA6/SPI1_MISO/ADC6/TIM3_CH1_22") (pintype "bidirectional"))
      (node (ref "IC7") (pin "1") (pinfunction "VOUTA_1") (pintype "output"))
      (node (ref "R31") (pin "2") (pinfunction "2_2") (pintype "passive"))
    )
    (net (code "18") (name "GEOMETRY_POT") (class "Default")
      (node (ref "IC2") (pin "10") (pinfunction "PC2/SPI2_MISO/ADC12_10") (pintype "bidirectional"))
      (node (ref "R10") (pin "P$2") (pinfunction "2_P$2") (pintype "passive"))
    )
    (net (code "19") (name "GND") (class "Default")
      (node (ref "C1") (pin "+") (pinfunction "+_+") (pintype "passive"))
      (node (ref "C10") (pin "2") (pinfunction "2_2") (pintype "passive"))
      (node (ref "C11") (pin "2") (pinfunction "2_2") (pintype "passive"))
      (node (ref "C12") (pin "-") (pinfunction "-_-") (pintype "passive"))
      (node (ref "C13") (pin "2") (pinfunction "2_2") (pintype "passive"))
      (node (ref "C15") (pin "2") (pinfunction "2_2") (pintype "passive"))
      (node (ref "C16") (pin "2") (pinfunction "2_2") (pintype "passive"))
      (node (ref "C17") (pin "2") (pinfunction "2_2") (pintype "passive"))
      (node (ref "C18") (pin "2") (pinfunction "2_2") (pintype "passive"))
      (node (ref "C19") (pin "2") (pinfunction "2_2") (pintype "passive"))
      (node (ref "C2") (pin "-") (pinfunction "-_-") (pintype "passive"))
      (node (ref "C20") (pin "2") (pinfunction "2_2") (pintype "passive"))
      (node (ref "C21") (pin "-") (pinfunction "-_-") (pintype "passive"))
      (node (ref "C22") (pin "2") (pinfunction "2_2") (pintype "passive"))
      (node (ref "C25") (pin "2") (pinfunction "2_2") (pintype "passive"))
      (node (ref "C27") (pin "2") (pinfunction "2_2") (pintype "passive"))
      (node (ref "C3") (pin "-") (pinfunction "-_-") (pintype "passive"))
      (node (ref "C30") (pin "2") (pinfunction "2_2") (pintype "passive"))
      (node (ref "C31") (pin "2") (pinfunction "2_2") (pintype "passive"))
      (node (ref "C34") (pin "-") (pinfunction "-_-") (pintype "passive"))
      (node (ref "C35") (pin "2") (pinfunction "2_2") (pintype "passive"))
      (node (ref "C37") (pin "2") (pinfunction "2_2") (pintype "passive"))
      (node (ref "C39") (pin "2") (pinfunction "2_2") (pintype "passive"))
      (node (ref "C41") (pin "-") (pinfunction "-_-") (pintype "passive"))
      (node (ref "C44") (pin "2") (pinfunction "2_2") (pintype "passive"))
      (node (ref "C45") (pin "1") (pinfunction "1_1") (pintype "passive"))
      (node (ref "C46") (pin "-") (pinfunction "-_-") (pintype "passive"))
      (node (ref "C47") (pin "2") (pinfunction "2_2") (pintype "passive"))
      (node (ref "C48") (pin "2") (pinfunction "2_2") (pintype "passive"))
      (node (ref "C49") (pin "2") (pinfunction "2_2") (pintype "passive"))
      (node (ref "C6") (pin "2") (pinfunction "2_2") (pintype "passive"))
      (node (ref "C7") (pin "2") (pinfunction "2_2") (pintype "passive"))
      (node (ref "C8") (pin "-") (pinfunction "-_-") (pintype "passive"))
      (node (ref "C9") (pin "2") (pinfunction "2_2") (pintype "passive"))
      (node (ref "D3") (pin "1") (pinfunction "A_1") (pintype "passive"))
      (node (ref "IC1") (pin "1") (pinfunction "GND_1") (pintype "power_in"))
      (node (ref "IC2") (pin "12") (pinfunction "VSSA_12") (pintype "power_in"))
      (node (ref "IC2") (pin "18") (pinfunction "VSS_4_18") (pintype "power_in"))
      (node (ref "IC2") (pin "26") (pinfunction "PB0/ADC8/TIM3_CH3_26") (pintype "bidirectional"))
      (node (ref "IC2") (pin "28") (pinfunction "PB2/BOOT1_28") (pintype "bidirectional"))
      (node (ref "IC2") (pin "63") (pinfunction "VSS_3_63") (pintype "power_in"))
      (node (ref "IC3") (pin "1") (pinfunction "C_1") (pintype "passive"))
      (node (ref "IC4") (pin "6") (pinfunction "INH_6") (pintype "input"))
      (node (ref "IC4") (pin "7") (pinfunction "VEE_7") (pintype "power_in"))
      (node (ref "IC4") (pin "8") (pinfunction "GND_8") (pintype "power_in"))
      (node (ref "IC5") (pin "3") (pinfunction "+IN_3") (pintype "input"))
      (node (ref "IC5") (pin "4") (pinfunction "V-_4") (pintype "power_in"))
      (node (ref "IC5") (pin "5") (pinfunction "+IN_5") (pintype "input"))
      (node (ref "IC6") (pin "11") (pinfunction "HPGND_11") (pintype "bidirectional"))
      (node (ref "IC6") (pin "15") (pinfunction "AGND_15") (pintype "bidirectional"))
      (node (ref "IC6") (pin "21") (pinfunction "MODE_21") (pintype "bidirectional"))
      (node (ref "IC6") (pin "22") (pinfunction "CSB_22") (pintype "bidirectional"))
      (node (ref "IC6") (pin "28") (pinfunction "DGND_28") (pintype "bidirectional"))
      (node (ref "IC7") (pin "10") (pinfunction "VINC+_10") (pintype "input"))
      (node (ref "IC7") (pin "11") (pinfunction "VSS_11") (pintype "power_in"))
      (node (ref "IC7") (pin "12") (pinfunction "VIND+_12") (pintype "input"))
      (node (ref "IC7") (pin "3") (pinfunction "VINA+_3") (pintype "input"))
      (node (ref "IC7") (pin "5") (pinfunction "VINB+_5") (pintype "input"))
      (node (ref "IC8") (pin "3") (pinfunction "+IN_3") (pintype "input"))
      (node (ref "IC8") (pin "5") (pinfunction "+IN_5") (pintype "input"))
      (node (ref "J1") (pin "P$3") (pinfunction "1_P$3") (pintype "passive"))
      (node (ref "J10") (pin "P$3") (pinfunction "1_P$3") (pintype "passive"))
      (node (ref "J2") (pin "P$3") (pinfunction "1_P$3") (pintype "passive"))
      (node (ref "J3") (pin "P$3") (pinfunction "1_P$3") (pintype "passive"))
      (node (ref "J4") (pin "P$3") (pinfunction "1_P$3") (pintype "passive"))
      (node (ref "J5") (pin "P$3") (pinfunction "1_P$3") (pintype "passive"))
      (node (ref "J6") (pin "P$3") (pinfunction "1_P$3") (pintype "passive"))
      (node (ref "J7") (pin "P$3") (pinfunction "1_P$3") (pintype "passive"))
      (node (ref "J8") (pin "P$3") (pinfunction "1_P$3") (pintype "passive"))
      (node (ref "J9") (pin "P$3") (pinfunction "1_P$3") (pintype "passive"))
      (node (ref "JP1") (pin "3") (pinfunction "3_3") (pintype "passive"))
      (node (ref "JP1") (pin "5") (pinfunction "5_5") (pintype "passive"))
      (node (ref "JP1") (pin "9") (pinfunction "9_9") (pintype "passive"))
      (node (ref "JP3") (pin "3") (pinfunction "3_3") (pintype "passive"))
      (node (ref "JP3") (pin "4") (pinfunction "4_4") (pintype "passive"))
      (node (ref "JP3") (pin "5") (pinfunction "5_5") (pintype "passive"))
      (node (ref "JP3") (pin "6") (pinfunction "6_6") (pintype "passive"))
      (node (ref "JP3") (pin "7") (pinfunction "7_7") (pintype "passive"))
      (node (ref "JP3") (pin "8") (pinfunction "8_8") (pintype "passive"))
      (node (ref "LED1") (pin "2") (pinfunction "C_2") (pintype "bidirectional"))
      (node (ref "LED2") (pin "2") (pinfunction "C_2") (pintype "bidirectional"))
      (node (ref "Q1") (pin "GND") (pinfunction "GND_GND") (pintype "bidirectional"))
      (node (ref "Q2") (pin "E") (pinfunction "E_E") (pintype "passive"))
      (node (ref "Q3") (pin "GND") (pinfunction "GND_GND") (pintype "bidirectional"))
      (node (ref "R10") (pin "P$1") (pinfunction "1_P$1") (pintype "passive"))
      (node (ref "R27") (pin "2") (pinfunction "2_2") (pintype "passive"))
      (node (ref "R28") (pin "P$1") (pinfunction "1_P$1") (pintype "passive"))
      (node (ref "R29") (pin "P$1") (pinfunction "1_P$1") (pintype "passive"))
      (node (ref "R30") (pin "P$1") (pinfunction "1_P$1") (pintype "passive"))
      (node (ref "R33") (pin "1") (pinfunction "1_1") (pintype "passive"))
      (node (ref "R38") (pin "1") (pinfunction "1_1") (pintype "passive"))
      (node (ref "R45") (pin "P$1") (pinfunction "1_P$1") (pintype "passive"))
      (node (ref "R46") (pin "P$1") (pinfunction "1_P$1") (pintype "passive"))
      (node (ref "R47") (pin "P$1") (pinfunction "1_P$1") (pintype "passive"))
      (node (ref "R48") (pin "P$1") (pinfunction "1_P$1") (pintype "passive"))
      (node (ref "R49") (pin "P$1") (pinfunction "1_P$1") (pintype "passive"))
      (node (ref "R51") (pin "1") (pinfunction "1_1") (pintype "passive"))
      (node (ref "R61") (pin "1") (pinfunction "1_1") (pintype "passive"))
      (node (ref "R9") (pin "P$1") (pinfunction "1_P$1") (pintype "passive"))
      (node (ref "SW1") (pin "1") (pinfunction "1_1") (pintype "passive"))
      (node (ref "SW1") (pin "2") (pinfunction "2_2") (pintype "passive"))
      (node (ref "SW2") (pin "1") (pinfunction "1_1") (pintype "passive"))
      (node (ref "SW2") (pin "2") (pinfunction "2_2") (pintype "passive"))
    )
    (net (code "20") (name "I2C_SCL") (class "Default")
      (node (ref "IC2") (pin "29") (pinfunction "PB10/SPI2_SCK/I2S_SCK/I2C2_SCL/USART3_TX_29") (pintype "bidirectional"))
      (node (ref "IC6") (pin "24") (pinfunction "SCLK_24") (pintype "bidirectional"))
      (node (ref "R16") (pin "1") (pinfunction "1_1") (pintype "passive"))
    )
    (net (code "21") (name "I2C_SDA") (class "Default")
      (node (ref "IC2") (pin "30") (pinfunction "PB11/I2C2_SDA/USART3_RX_30") (pintype "bidirectional"))
      (node (ref "IC6") (pin "23") (pinfunction "SDIN_23") (pintype "bidirectional"))
      (node (ref "R17") (pin "1") (pinfunction "1_1") (pintype "passive"))
    )
    (net (code "22") (name "I2S_LRCK") (class "Default")
      (node (ref "IC2") (pin "33") (pinfunction "PB12/SPI2_NSS/I2S2_WS/I2C2_SMBA/USART3_CK/TIM1_BKIN_33") (pintype "bidirectional"))
      (node (ref "IC6") (pin "5") (pinfunction "DACLRC_5") (pintype "bidirectional"))
      (node (ref "IC6") (pin "7") (pinfunction "ADCLRC_7") (pintype "bidirectional"))
    )
    (net (code "23") (name "I2S_SCK") (class "Default")
      (node (ref "IC2") (pin "34") (pinfunction "PB13/SPI2_SCK/I2S2_SCK/USART3_CTS/TIM1_CH1N_34") (pintype "bidirectional"))
      (node (ref "IC6") (pin "3") (pinfunction "BCLK_3") (pintype "bidirectional"))
    )
    (net (code "24") (name "I2S_SIN") (class "Default")
      (node (ref "IC2") (pin "35") (pinfunction "PB14/SPI2_MISO/USART3_RTS/TIM1_CH2N_35") (pintype "bidirectional"))
      (node (ref "IC6") (pin "6") (pinfunction "ADCDAT_6") (pintype "bidirectional"))
    )
    (net (code "25") (name "I2S_SOUT") (class "Default")
      (node (ref "IC2") (pin "36") (pinfunction "PB15/SPI2_MOSI/I2S2_SD/TIM1_CH3N_36") (pintype "bidirectional"))
      (node (ref "IC6") (pin "4") (pinfunction "DACDAT_4") (pintype "bidirectional"))
    )
    (net (code "26") (name "IN_1") (class "Default")
      (node (ref "IC6") (pin "20") (pinfunction "LLINEIN_20") (pintype "bidirectional"))
      (node (ref "R27") (pin "1") (pinfunction "1_1") (pintype "passive"))
    )
    (net (code "27") (name "IN_2") (class "Default")
      (node (ref "C40") (pin "+") (pinfunction "+_+") (pintype "passive"))
      (node (ref "IC6") (pin "19") (pinfunction "RLINEIN_19") (pintype "bidirectional"))
    )
    (net (code "28") (name "JTCK") (class "Default")
      (node (ref "IC2") (pin "49") (pinfunction "PA14/JTCK-SWCLK_49") (pintype "bidirectional"))
      (node (ref "JP1") (pin "4") (pinfunction "4_4") (pintype "passive"))
    )
    (net (code "29") (name "JTDI") (class "Default")
      (node (ref "IC2") (pin "50") (pinfunction "PA15/JTDI/SPI3_NSS/I2S3_WS_50") (pintype "bidirectional"))
      (node (ref "JP1") (pin "8") (pinfunction "8_8") (pintype "passive"))
    )
    (net (code "30") (name "JTDO") (class "Default")
      (node (ref "IC2") (pin "55") (pinfunction "PB3/JTDO/SPI3_SCK/I2S3_SCK_55") (pintype "bidirectional"))
      (node (ref "JP1") (pin "6") (pinfunction "6_6") (pintype "passive"))
    )
    (net (code "31") (name "JTMS") (class "Default")
      (node (ref "IC2") (pin "46") (pinfunction "PA13/JTMS-SWDAT_46") (pintype "bidirectional"))
      (node (ref "JP1") (pin "2") (pinfunction "2_2") (pintype "passive"))
    )
    (net (code "32") (name "MAIN_OUT") (class "Default")
      (node (ref "C32") (pin "+") (pinfunction "+_+") (pintype "passive"))
      (node (ref "IC6") (pin "12") (pinfunction "LOUT_12") (pintype "bidirectional"))
    )
    (net (code "33") (name "MUXED_POTS") (class "Default")
      (node (ref "IC2") (pin "9") (pinfunction "PC1/ADC11_9") (pintype "bidirectional"))
      (node (ref "IC4") (pin "3") (pinfunction "X_3") (pintype "bidirectional"))
    )
    (net (code "34") (name "MUX_ADDR_0") (class "Default")
      (node (ref "IC2") (pin "59") (pinfunction "PB7/I2C1_SDA/TIM4_CH2/USART1_RX_59") (pintype "bidirectional"))
      (node (ref "IC4") (pin "11") (pinfunction "A_11") (pintype "input"))
    )
    (net (code "35") (name "MUX_ADDR_1") (class "Default")
      (node (ref "IC2") (pin "58") (pinfunction "PB6/I2C1_SCL/TIM4_CH1/USART1_TX_58") (pintype "bidirectional"))
      (node (ref "IC4") (pin "10") (pinfunction "B_10") (pintype "input"))
    )
    (net (code "36") (name "MUX_ADDR_2") (class "Default")
      (node (ref "IC2") (pin "57") (pinfunction "PB5/I2C1_SMBA/SPI1_MOSI/SPI3_MOSI/I2S3_SD_57") (pintype "bidirectional"))
      (node (ref "IC4") (pin "9") (pinfunction "C_9") (pintype "input"))
    )
    (net (code "37") (name "NORMALIZATION_PROBE") (class "Default")
      (node (ref "D3") (pin "3") (pinfunction "AC_3") (pintype "passive"))
      (node (ref "IC2") (pin "39") (pinfunction "PC8_39") (pintype "bidirectional"))
      (node (ref "R52") (pin "1") (pinfunction "1_1") (pintype "passive"))
      (node (ref "R53") (pin "1") (pinfunction "1_1") (pintype "passive"))
      (node (ref "R57") (pin "1") (pinfunction "1_1") (pintype "passive"))
    )
    (net (code "38") (name "Net-(C32-Pad-)") (class "Default")
      (node (ref "C32") (pin "-") (pinfunction "-_-") (pintype "passive"))
      (node (ref "R33") (pin "2") (pinfunction "2_2") (pintype "passive"))
      (node (ref "R40") (pin "2") (pinfunction "2_2") (pintype "passive"))
    )
    (net (code "39") (name "Net-(C33-Pad-)") (class "Default")
      (node (ref "C33") (pin "-") (pinfunction "-_-") (pintype "passive"))
      (node (ref "R38") (pin "2") (pinfunction "2_2") (pintype "passive"))
      (node (ref "R43") (pin "2") (pinfunction "2_2") (pintype "passive"))
    )
    (net (code "40") (name "Net-(C40-Pad-)") (class "Default")
      (node (ref "C40") (pin "-") (pinfunction "-_-") (pintype "passive"))
      (node (ref "C49") (pin "1") (pinfunction "1_1") (pintype "passive"))
      (node (ref "R51") (pin "2") (pinfunction "2_2") (pintype "passive"))
      (node (ref "R54") (pin "1") (pinfunction "1_1") (pintype "passive"))
    )
    (net (code "41") (name "Net-(D1-PadA)") (class "Default")
      (node (ref "D1") (pin "A") (pinfunction "A_A") (pintype "passive"))
      (node (ref "L1") (pin "1") (pinfunction "1_1") (pintype "passive"))
    )
    (net (code "42") (name "Net-(D2-PadC)") (class "Default")
      (node (ref "D2") (pin "C") (pinfunction "C_C") (pintype "passive"))
      (node (ref "L2") (pin "1") (pinfunction "1_1") (pintype "passive"))
    )
    (net (code "43") (name "Net-(IC1-VIN)") (class "Default")
      (node (ref "C2") (pin "+") (pinfunction "+_+") (pintype "passive"))
      (node (ref "IC1") (pin "2") (pinfunction "VIN_2") (pintype "input"))
      (node (ref "R2") (pin "1") (pinfunction "1_1") (pintype "passive"))
    )
    (net (code "44") (name "Net-(IC2-PC0{slash}ADC10)") (class "Default")
      (node (ref "IC2") (pin "8") (pinfunction "PC0/ADC10_8") (pintype "bidirectional"))
      (node (ref "R4") (pin "1") (pinfunction "1_1") (pintype "passive"))
    )
    (net (code "45") (name "Net-(IC2-PC10{slash}SPI3_SCK{slash}I2S3_SCK{slash}UART4_TX)") (class "Default")
      (node (ref "IC2") (pin "51") (pinfunction "PC10/SPI3_SCK/I2S3_SCK/UART4_TX_51") (pintype "bidirectional"))
      (node (ref "R5") (pin "1") (pinfunction "1_1") (pintype "passive"))
    )
    (net (code "46") (name "Net-(IC2-PC11{slash}UART4_RX{slash}SPI3_MISO{slash}USART3_RX)") (class "Default")
      (node (ref "IC2") (pin "52") (pinfunction "PC11/UART4_RX/SPI3_MISO/USART3_RX_52") (pintype "bidirectional"))
      (node (ref "R3") (pin "1") (pinfunction "1_1") (pintype "passive"))
    )
    (net (code "47") (name "Net-(IC2-PC12{slash}UART5_TX{slash}I2S3_SD{slash}USART3_CK)") (class "Default")
      (node (ref "IC2") (pin "53") (pinfunction "PC12/UART5_TX/I2S3_SD/USART3_CK_53") (pintype "bidirectional"))
      (node (ref "R1") (pin "1") (pinfunction "1_1") (pintype "passive"))
    )
    (net (code "48") (name "Net-(IC2-PD0{slash}OSC_IN)") (class "Default")
      (node (ref "IC2") (pin "5") (pinfunction "PD0/OSC_IN_5") (pintype "bidirectional"))
      (node (ref "Q1") (pin "X2") (pinfunction "X2_X2") (pintype "bidirectional"))
    )
    (net (code "49") (name "Net-(IC2-PD1{slash}OSC_OUT)") (class "Default")
      (node (ref "IC2") (pin "6") (pinfunction "PD1/OSC_OUT_6") (pintype "bidirectional"))
      (node (ref "Q1") (pin "X1") (pinfunction "X1_X1") (pintype "bidirectional"))
    )
    (net (code "50") (name "Net-(IC2-VCAP_1)") (class "Default")
      (node (ref "C16") (pin "1") (pinfunction "1_1") (pintype "passive"))
      (node (ref "IC2") (pin "31") (pinfunction "VCAP_1_31") (pintype "power_in"))
    )
    (net (code "51") (name "Net-(IC2-VCAP_2)") (class "Default")
      (node (ref "C22") (pin "1") (pinfunction "1_1") (pintype "passive"))
      (node (ref "IC2") (pin "47") (pinfunction "VCAP_2_47") (pintype "power_in"))
    )
    (net (code "52") (name "Net-(IC5A--IN)") (class "Default")
      (node (ref "C26") (pin "1") (pinfunction "1_1") (pintype "passive"))
      (node (ref "IC5") (pin "2") (pinfunction "-IN_2") (pintype "input"))
      (node (ref "R18") (pin "2") (pinfunction "2_2") (pintype "passive"))
      (node (ref "R19") (pin "1") (pinfunction "1_1") (pintype "passive"))
      (node (ref "R20") (pin "1") (pinfunction "1_1") (pintype "passive"))
    )
    (net (code "53") (name "Net-(IC5B--IN)") (class "Default")
      (node (ref "C14") (pin "1") (pinfunction "1_1") (pintype "passive"))
      (node (ref "IC5") (pin "6") (pinfunction "-IN_6") (pintype "input"))
      (node (ref "R13") (pin "2") (pinfunction "2_2") (pintype "passive"))
      (node (ref "R14") (pin "1") (pinfunction "1_1") (pintype "passive"))
      (node (ref "R15") (pin "1") (pinfunction "1_1") (pintype "passive"))
    )
    (net (code "54") (name "Net-(IC6-VMID)") (class "Default")
      (node (ref "C34") (pin "+") (pinfunction "+_+") (pintype "passive"))
      (node (ref "C35") (pin "1") (pinfunction "1_1") (pintype "passive"))
      (node (ref "IC6") (pin "16") (pinfunction "VMID_16") (pintype "bidirectional"))
    )
    (net (code "55") (name "Net-(IC6-XTI{slash}MCLK)") (class "Default")
      (node (ref "IC6") (pin "25") (pinfunction "XTI/MCLK_25") (pintype "bidirectional"))
      (node (ref "Q3") (pin "X1") (pinfunction "X1_X1") (pintype "bidirectional"))
    )
    (net (code "56") (name "Net-(IC6-XTO)") (class "Default")
      (node (ref "IC6") (pin "26") (pinfunction "XTO_26") (pintype "bidirectional"))
      (node (ref "Q3") (pin "X2") (pinfunction "X2_X2") (pintype "bidirectional"))
    )
    (net (code "57") (name "Net-(IC7-VINA-)") (class "Default")
      (node (ref "C36") (pin "1") (pinfunction "1_1") (pintype "passive"))
      (node (ref "IC7") (pin "2") (pinfunction "VINA-_2") (pintype "input"))
      (node (ref "R31") (pin "1") (pinfunction "1_1") (pintype "passive"))
      (node (ref "R34") (pin "2") (pinfunction "2_2") (pintype "passive"))
      (node (ref "R36") (pin "2") (pinfunction "2_2") (pintype "passive"))
    )
    (net (code "58") (name "Net-(IC7-VINB-)") (class "Default")
      (node (ref "C38") (pin "1") (pinfunction "1_1") (pintype "passive"))
      (node (ref "IC7") (pin "6") (pinfunction "VINB-_6") (pintype "input"))
      (node (ref "R32") (pin "1") (pinfunction "1_1") (pintype "passive"))
      (node (ref "R35") (pin "2") (pinfunction "2_2") (pintype "passive"))
      (node (ref "R37") (pin "2") (pinfunction "2_2") (pintype "passive"))
    )
    (net (code "59") (name "Net-(IC7-VINC-)") (class "Default")
      (node (ref "C29") (pin "2") (pinfunction "2_2") (pintype "passive"))
      (node (ref "IC7") (pin "9") (pinfunction "VINC-_9") (pintype "input"))
      (node (ref "R22") (pin "1") (pinfunction "1_1") (pintype "passive"))
      (node (ref "R24") (pin "1") (pinfunction "1_1") (pintype "passive"))
      (node (ref "R26") (pin "2") (pinfunction "2_2") (pintype "passive"))
    )
    (net (code "60") (name "Net-(IC7-VIND-)") (class "Default")
      (node (ref "C28") (pin "2") (pinfunction "2_2") (pintype "passive"))
      (node (ref "IC7") (pin "13") (pinfunction "VIND-_13") (pintype "input"))
      (node (ref "R21") (pin "1") (pinfunction "1_1") (pintype "passive"))
      (node (ref "R23") (pin "1") (pinfunction "1_1") (pintype "passive"))
      (node (ref "R25") (pin "2") (pinfunction "2_2") (pintype "passive"))
    )
    (net (code "61") (name "Net-(IC8A--IN)") (class "Default")
      (node (ref "C42") (pin "1") (pinfunction "1_1") (pintype "passive"))
      (node (ref "IC8") (pin "2") (pinfunction "-IN_2") (pintype "input"))
      (node (ref "R39") (pin "1") (pinfunction "1_1") (pintype "passive"))
      (node (ref "R40") (pin "1") (pinfunction "1_1") (pintype "passive"))
      (node (ref "R41") (pin "2") (pinfunction "2_2") (pintype "passive"))
    )
    (net (code "62") (name "Net-(IC8A-OUT)") (class "Default")
      (node (ref "C42") (pin "2") (pinfunction "2_2") (pintype "passive"))
      (node (ref "IC8") (pin "1") (pinfunction "OUT_1") (pintype "output"))
      (node (ref "R41") (pin "1") (pinfunction "1_1") (pintype "passive"))
      (node (ref "R55") (pin "2") (pinfunction "2_2") (pintype "passive"))
    )
    (net (code "63") (name "Net-(IC8B--IN)") (class "Default")
      (node (ref "C43") (pin "1") (pinfunction "1_1") (pintype "passive"))
      (node (ref "IC8") (pin "6") (pinfunction "-IN_6") (pintype "input"))
      (node (ref "R42") (pin "2") (pinfunction "2_2") (pintype "passive"))
      (node (ref "R43") (pin "1") (pinfunction "1_1") (pintype "passive"))
      (node (ref "R44") (pin "1") (pinfunction "1_1") (pintype "passive"))
    )
    (net (code "64") (name "Net-(IC8B-OUT)") (class "Default")
      (node (ref "C43") (pin "2") (pinfunction "2_2") (pintype "passive"))
      (node (ref "IC8") (pin "7") (pinfunction "OUT_7") (pintype "output"))
      (node (ref "R42") (pin "1") (pinfunction "1_1") (pintype "passive"))
      (node (ref "R56") (pin "2") (pinfunction "2_2") (pintype "passive"))
    )
    (net (code "65") (name "Net-(J1-2)") (class "Default")
      (node (ref "J1") (pin "P$1") (pinfunction "2_P$1") (pintype "passive"))
      (node (ref "R19") (pin "2") (pinfunction "2_2") (pintype "passive"))
    )
    (net (code "66") (name "Net-(J2-2)") (class "Default")
      (node (ref "J2") (pin "P$1") (pinfunction "2_P$1") (pintype "passive"))
      (node (ref "R22") (pin "2") (pinfunction "2_2") (pintype "passive"))
    )
    (net (code "67") (name "Net-(J2-3)") (class "Default")
      (node (ref "J2") (pin "P$2") (pinfunction "3_P$2") (pintype "passive"))
      (node (ref "R50") (pin "2") (pinfunction "2_2") (pintype "passive"))
    )
    (net (code "68") (name "Net-(J3-2)") (class "Default")
      (node (ref "J3") (pin "P$1") (pinfunction "2_P$1") (pintype "passive"))
      (node (ref "R21") (pin "2") (pinfunction "2_2") (pintype "passive"))
    )
    (net (code "69") (name "Net-(J4-2)") (class "Default")
      (node (ref "J4") (pin "P$1") (pinfunction "2_P$1") (pintype "passive"))
      (node (ref "R34") (pin "1") (pinfunction "1_1") (pintype "passive"))
    )
    (net (code "70") (name "Net-(J5-2)") (class "Default")
      (node (ref "J5") (pin "P$1") (pinfunction "2_P$1") (pintype "passive"))
      (node (ref "R35") (pin "1") (pinfunction "1_1") (pintype "passive"))
    )
    (net (code "71") (name "Net-(J6-2)") (class "Default")
      (node (ref "J6") (pin "P$1") (pinfunction "2_P$1") (pintype "passive"))
      (node (ref "R11") (pin "1") (pinfunction "1_1") (pintype "passive"))
    )
    (net (code "72") (name "Net-(J6-3)") (class "Default")
      (node (ref "J6") (pin "P$2") (pinfunction "3_P$2") (pintype "passive"))
      (node (ref "R52") (pin "2") (pinfunction "2_2") (pintype "passive"))
    )
    (net (code "73") (name "Net-(J7-2)") (class "Default")
      (node (ref "J7") (pin "P$1") (pinfunction "2_P$1") (pintype "passive"))
      (node (ref "R14") (pin "2") (pinfunction "2_2") (pintype "passive"))
    )
    (net (code "74") (name "Net-(J8-2)") (class "Default")
      (node (ref "J8") (pin "P$1") (pinfunction "2_P$1") (pintype "passive"))
      (node (ref "R54") (pin "2") (pinfunction "2_2") (pintype "passive"))
    )
    (net (code "75") (name "Net-(J8-3)") (class "Default")
      (node (ref "J8") (pin "P$2") (pinfunction "3_P$2") (pintype "passive"))
      (node (ref "R53") (pin "2") (pinfunction "2_2") (pintype "passive"))
    )
    (net (code "76") (name "Net-(J9-2)") (class "Default")
      (node (ref "J9") (pin "P$1") (pinfunction "2_P$1") (pintype "passive"))
      (node (ref "R55") (pin "1") (pinfunction "1_1") (pintype "passive"))
    )
    (net (code "77") (name "Net-(J9-3)") (class "Default")
      (node (ref "J9") (pin "P$2") (pinfunction "3_P$2") (pintype "passive"))
      (node (ref "SJ1") (pin "2") (pinfunction "2_2") (pintype "passive"))
    )
    (net (code "78") (name "Net-(J10-2)") (class "Default")
      (node (ref "J10") (pin "P$1") (pinfunction "2_P$1") (pintype "passive"))
      (node (ref "R56") (pin "1") (pinfunction "1_1") (pintype "passive"))
    )
    (net (code "79") (name "Net-(J10-3)") (class "Default")
      (node (ref "J10") (pin "P$2") (pinfunction "3_P$2") (pintype "passive"))
      (node (ref "R39") (pin "2") (pinfunction "2_2") (pintype "passive"))
    )
    (net (code "80") (name "Net-(JP3-Pad1)") (class "Default")
      (node (ref "JP3") (pin "1") (pinfunction "1_1") (pintype "passive"))
      (node (ref "JP3") (pin "2") (pinfunction "2_2") (pintype "passive"))
      (node (ref "L1") (pin "2") (pinfunction "2_2") (pintype "passive"))
    )
    (net (code "81") (name "Net-(JP3-Pad10)") (class "Default")
      (node (ref "JP3") (pin "10") (pinfunction "10_10") (pintype "passive"))
      (node (ref "JP3") (pin "9") (pinfunction "9_9") (pintype "passive"))
      (node (ref "L2") (pin "2") (pinfunction "2_2") (pintype "passive"))
    )
    (net (code "82") (name "Net-(LED1-GRN)") (class "Default")
      (node (ref "LED1") (pin "1") (pinfunction "GRN_1") (pintype "bidirectional"))
      (node (ref "R3") (pin "2") (pinfunction "2_2") (pintype "passive"))
    )
    (net (code "83") (name "Net-(LED1-RED)") (class "Default")
      (node (ref "LED1") (pin "3") (pinfunction "RED_3") (pintype "bidirectional"))
      (node (ref "R1") (pin "2") (pinfunction "2_2") (pintype "passive"))
    )
    (net (code "84") (name "Net-(LED2-GRN)") (class "Default")
      (node (ref "LED2") (pin "1") (pinfunction "GRN_1") (pintype "bidirectional"))
      (node (ref "R5") (pin "2") (pinfunction "2_2") (pintype "passive"))
    )
    (net (code "85") (name "Net-(LED2-RED)") (class "Default")
      (node (ref "LED2") (pin "3") (pinfunction "RED_3") (pintype "bidirectional"))
      (node (ref "R4") (pin "2") (pinfunction "2_2") (pintype "passive"))
    )
    (net (code "86") (name "Net-(Q2-PadB)") (class "Default")
      (node (ref "Q2") (pin "B") (pinfunction "B_B") (pintype "passive"))
      (node (ref "R11") (pin "2") (pinfunction "2_2") (pintype "passive"))
    )
    (net (code "87") (name "Net-(R44-Pad2)") (class "Default")
      (node (ref "R44") (pin "2") (pinfunction "2_2") (pintype "passive"))
      (node (ref "SJ1") (pin "1") (pinfunction "1_1") (pintype "passive"))
    )
    (net (code "88") (name "POSITION_ATT") (class "Default")
      (node (ref "IC4") (pin "15") (pinfunction "X2_15") (pintype "bidirectional"))
      (node (ref "R49") (pin "P$2") (pinfunction "2_P$2") (pintype "passive"))
    )
    (net (code "89") (name "POSITION_CV") (class "Default")
      (node (ref "C38") (pin "2") (pinfunction "2_2") (pintype "passive"))
      (node (ref "IC2") (pin "23") (pinfunction "PA7/SPI1_MOSI/ADC7/TIM3_CH2_23") (pintype "bidirectional"))
      (node (ref "IC7") (pin "7") (pinfunction "VOUTB_7") (pintype "output"))
      (node (ref "R32") (pin "2") (pinfunction "2_2") (pintype "passive"))
    )
    (net (code "90") (name "POSITION_POT") (class "Default")
      (node (ref "IC4") (pin "12") (pinfunction "X3_12") (pintype "bidirectional"))
      (node (ref "R30") (pin "P$2") (pinfunction "2_P$2") (pintype "passive"))
    )
    (net (code "91") (name "RESET") (class "Default")
      (node (ref "IC2") (pin "7") (pinfunction "NRST_7") (pintype "bidirectional"))
      (node (ref "JP1") (pin "10") (pinfunction "10_10") (pintype "passive"))
      (node (ref "R60") (pin "1") (pinfunction "1_1") (pintype "passive"))
    )
    (net (code "92") (name "RX") (class "Default")
      (node (ref "IC2") (pin "43") (pinfunction "PA10/USART1_RX/TIM1_CH3_43") (pintype "bidirectional"))
    )
    (net (code "93") (name "STRUM") (class "Default")
      (node (ref "IC2") (pin "16") (pinfunction "PA2/USART2_TX/ADC2/TIM2_CH3_16") (pintype "bidirectional"))
      (node (ref "Q2") (pin "C") (pinfunction "C_C") (pintype "passive"))
      (node (ref "R8") (pin "1") (pinfunction "1_1") (pintype "passive"))
    )
    (net (code "94") (name "SW_MODE") (class "Default")
      (node (ref "IC2") (pin "61") (pinfunction "PB8/TIM4_CH3/I2C1_SCL_61") (pintype "bidirectional"))
      (node (ref "SW2") (pin "3") (pinfunction "3_3") (pintype "passive"))
      (node (ref "SW2") (pin "4") (pinfunction "4_4") (pintype "passive"))
    )
    (net (code "95") (name "SW_POLYPHONY") (class "Default")
      (node (ref "IC2") (pin "62") (pinfunction "PB9/SPI2_NSS/I2S2_WS/I2C1_SDA/TIM4_CH4_62") (pintype "bidirectional"))
      (node (ref "SW1") (pin "3") (pinfunction "3_3") (pintype "passive"))
      (node (ref "SW1") (pin "4") (pinfunction "4_4") (pintype "passive"))
    )
    (net (code "96") (name "TX") (class "Default")
      (node (ref "IC2") (pin "42") (pinfunction "PA9/USART1_TX/TIM1_CH2_42") (pintype "bidirectional"))
    )
    (net (code "97") (name "VBAT") (class "Default")
      (node (ref "IC2") (pin "1") (pinfunction "VBAT_1") (pintype "power_in"))
    )
    (net (code "98") (name "VCC") (class "Default")
      (node (ref "C3") (pin "+") (pinfunction "+_+") (pintype "passive"))
      (node (ref "C39") (pin "1") (pinfunction "1_1") (pintype "passive"))
      (node (ref "D1") (pin "C") (pinfunction "C_C") (pintype "passive"))
      (node (ref "IC8") (pin "8") (pinfunction "V+_8") (pintype "power_in"))
      (node (ref "R2") (pin "2") (pinfunction "2_2") (pintype "passive"))
    )
    (net (code "99") (name "VEE") (class "Default")
      (node (ref "C1") (pin "-") (pinfunction "-_-") (pintype "passive"))
      (node (ref "C45") (pin "2") (pinfunction "2_2") (pintype "passive"))
      (node (ref "D2") (pin "A") (pinfunction "A_A") (pintype "passive"))
      (node (ref "IC8") (pin "4") (pinfunction "V-_4") (pintype "power_in"))
      (node (ref "R12") (pin "1") (pinfunction "1_1") (pintype "passive"))
    )
    (net (code "100") (name "V_OCT_CV") (class "Default")
      (node (ref "C14") (pin "2") (pinfunction "2_2") (pintype "passive"))
      (node (ref "IC2") (pin "15") (pinfunction "PA1/USART2_RTS/UART4_RX/ADC1/TIM2_CH2_15") (pintype "bidirectional"))
      (node (ref "IC5") (pin "7") (pinfunction "OUT_7") (pintype "output"))
      (node (ref "R13") (pin "1") (pinfunction "1_1") (pintype "passive"))
    )
    (net (code "101") (name "unconnected-(IC2-PA3{slash}USART2_RX{slash}ADC3{slash}TIM2_CH4-Pad17)") (class "Default")
      (node (ref "IC2") (pin "17") (pinfunction "PA3/USART2_RX/ADC3/TIM2_CH4_17") (pintype "bidirectional"))
    )
    (net (code "102") (name "unconnected-(IC2-PA8{slash}USART1_CK{slash}TIM1_CH1{slash}MCO-Pad41)") (class "Default")
      (node (ref "IC2") (pin "41") (pinfunction "PA8/USART1_CK/TIM1_CH1/MCO_41") (pintype "bidirectional"))
    )
    (net (code "103") (name "unconnected-(IC2-PA11{slash}USART1_CTS{slash}CANRX{slash}USBDM{slash}TIM1_CH4-Pad44)") (class "Default")
      (node (ref "IC2") (pin "44") (pinfunction "PA11/USART1_CTS/CANRX/USBDM/TIM1_CH4_44") (pintype "bidirectional"))
    )
    (net (code "104") (name "unconnected-(IC2-PA12{slash}USART1_RTS{slash}CANTX{slash}USBDP{slash}TIM1_ETR-Pad45)") (class "Default")
      (node (ref "IC2") (pin "45") (pinfunction "PA12/USART1_RTS/CANTX/USBDP/TIM1_ETR_45") (pintype "bidirectional"))
    )
    (net (code "105") (name "unconnected-(IC2-PB1{slash}ADC9{slash}TIM3_CH4-Pad27)") (class "Default")
      (node (ref "IC2") (pin "27") (pinfunction "PB1/ADC9/TIM3_CH4_27") (pintype "bidirectional"))
    )
    (net (code "106") (name "unconnected-(IC2-PB4{slash}NJTRST{slash}SPI3_MISO{slash}SPI1_MISO-Pad56)") (class "Default")
      (node (ref "IC2") (pin "56") (pinfunction "PB4/NJTRST/SPI3_MISO/SPI1_MISO_56") (pintype "bidirectional"))
    )
    (net (code "107") (name "unconnected-(IC2-PC4{slash}ADC14-Pad24)") (class "Default")
      (node (ref "IC2") (pin "24") (pinfunction "PC4/ADC14_24") (pintype "bidirectional"))
    )
    (net (code "108") (name "unconnected-(IC2-PC5{slash}ADC15-Pad25)") (class "Default")
      (node (ref "IC2") (pin "25") (pinfunction "PC5/ADC15_25") (pintype "bidirectional"))
    )
    (net (code "109") (name "unconnected-(IC2-PC6{slash}I2S2_MCK-Pad37)") (class "Default")
      (node (ref "IC2") (pin "37") (pinfunction "PC6/I2S2_MCK_37") (pintype "bidirectional"))
    )
    (net (code "110") (name "unconnected-(IC2-PC7{slash}I2S3_MCK-Pad38)") (class "Default")
      (node (ref "IC2") (pin "38") (pinfunction "PC7/I2S3_MCK_38") (pintype "bidirectional"))
    )
    (net (code "111") (name "unconnected-(IC2-PC9{slash}I2S2_CKIN{slash}I2S3_CKIN-Pad40)") (class "Default")
      (node (ref "IC2") (pin "40") (pinfunction "PC9/I2S2_CKIN/I2S3_CKIN_40") (pintype "bidirectional"))
    )
    (net (code "112") (name "unconnected-(IC2-PC13-TAMPER-RTC-Pad2)") (class "Default")
      (node (ref "IC2") (pin "2") (pinfunction "PC13-TAMPER-RTC_2") (pintype "bidirectional"))
    )
    (net (code "113") (name "unconnected-(IC2-PC14{slash}OSC32_IN-Pad3)") (class "Default")
      (node (ref "IC2") (pin "3") (pinfunction "PC14/OSC32_IN_3") (pintype "bidirectional"))
    )
    (net (code "114") (name "unconnected-(IC2-PC15{slash}OSC_OUT-Pad4)") (class "Default")
      (node (ref "IC2") (pin "4") (pinfunction "PC15/OSC_OUT_4") (pintype "bidirectional"))
    )
    (net (code "115") (name "unconnected-(IC2-PD2{slash}TIM3-ETR-Pad54)") (class "Default")
      (node (ref "IC2") (pin "54") (pinfunction "PD2/TIM3-ETR_54") (pintype "bidirectional"))
    )
    (net (code "116") (name "unconnected-(IC6-CLKOUT-Pad2)") (class "Default")
      (node (ref "IC6") (pin "2") (pinfunction "CLKOUT_2") (pintype "bidirectional"))
    )
    (net (code "117") (name "unconnected-(IC6-LHPOUT-Pad9)") (class "Default")
      (node (ref "IC6") (pin "9") (pinfunction "LHPOUT_9") (pintype "bidirectional"))
    )
    (net (code "118") (name "unconnected-(IC6-MICBIAS-Pad17)") (class "Default")
      (node (ref "IC6") (pin "17") (pinfunction "MICBIAS_17") (pintype "bidirectional"))
    )
    (net (code "119") (name "unconnected-(IC6-MICIN-Pad18)") (class "Default")
      (node (ref "IC6") (pin "18") (pinfunction "MICIN_18") (pintype "bidirectional"))
    )
    (net (code "120") (name "unconnected-(IC6-RHPOUT-Pad10)") (class "Default")
      (node (ref "IC6") (pin "10") (pinfunction "RHPOUT_10") (pintype "bidirectional"))
    )
    (net (code "121") (name "unconnected-(J1-3-PadP$2)") (class "Default")
      (node (ref "J1") (pin "P$2") (pinfunction "3_P$2") (pintype "passive"))
    )
    (net (code "122") (name "unconnected-(J3-3-PadP$2)") (class "Default")
      (node (ref "J3") (pin "P$2") (pinfunction "3_P$2") (pintype "passive"))
    )
    (net (code "123") (name "unconnected-(J4-3-PadP$2)") (class "Default")
      (node (ref "J4") (pin "P$2") (pinfunction "3_P$2") (pintype "passive"))
    )
    (net (code "124") (name "unconnected-(J5-3-PadP$2)") (class "Default")
      (node (ref "J5") (pin "P$2") (pinfunction "3_P$2") (pintype "passive"))
    )
    (net (code "125") (name "unconnected-(JP1-Pad7)") (class "Default")
      (node (ref "JP1") (pin "7") (pinfunction "7_7") (pintype "passive"))
    )
  )
)
